# Copy_of_EP1C6T144I8N.net
KiCad netlist of a schematic drawn in Altium Designer
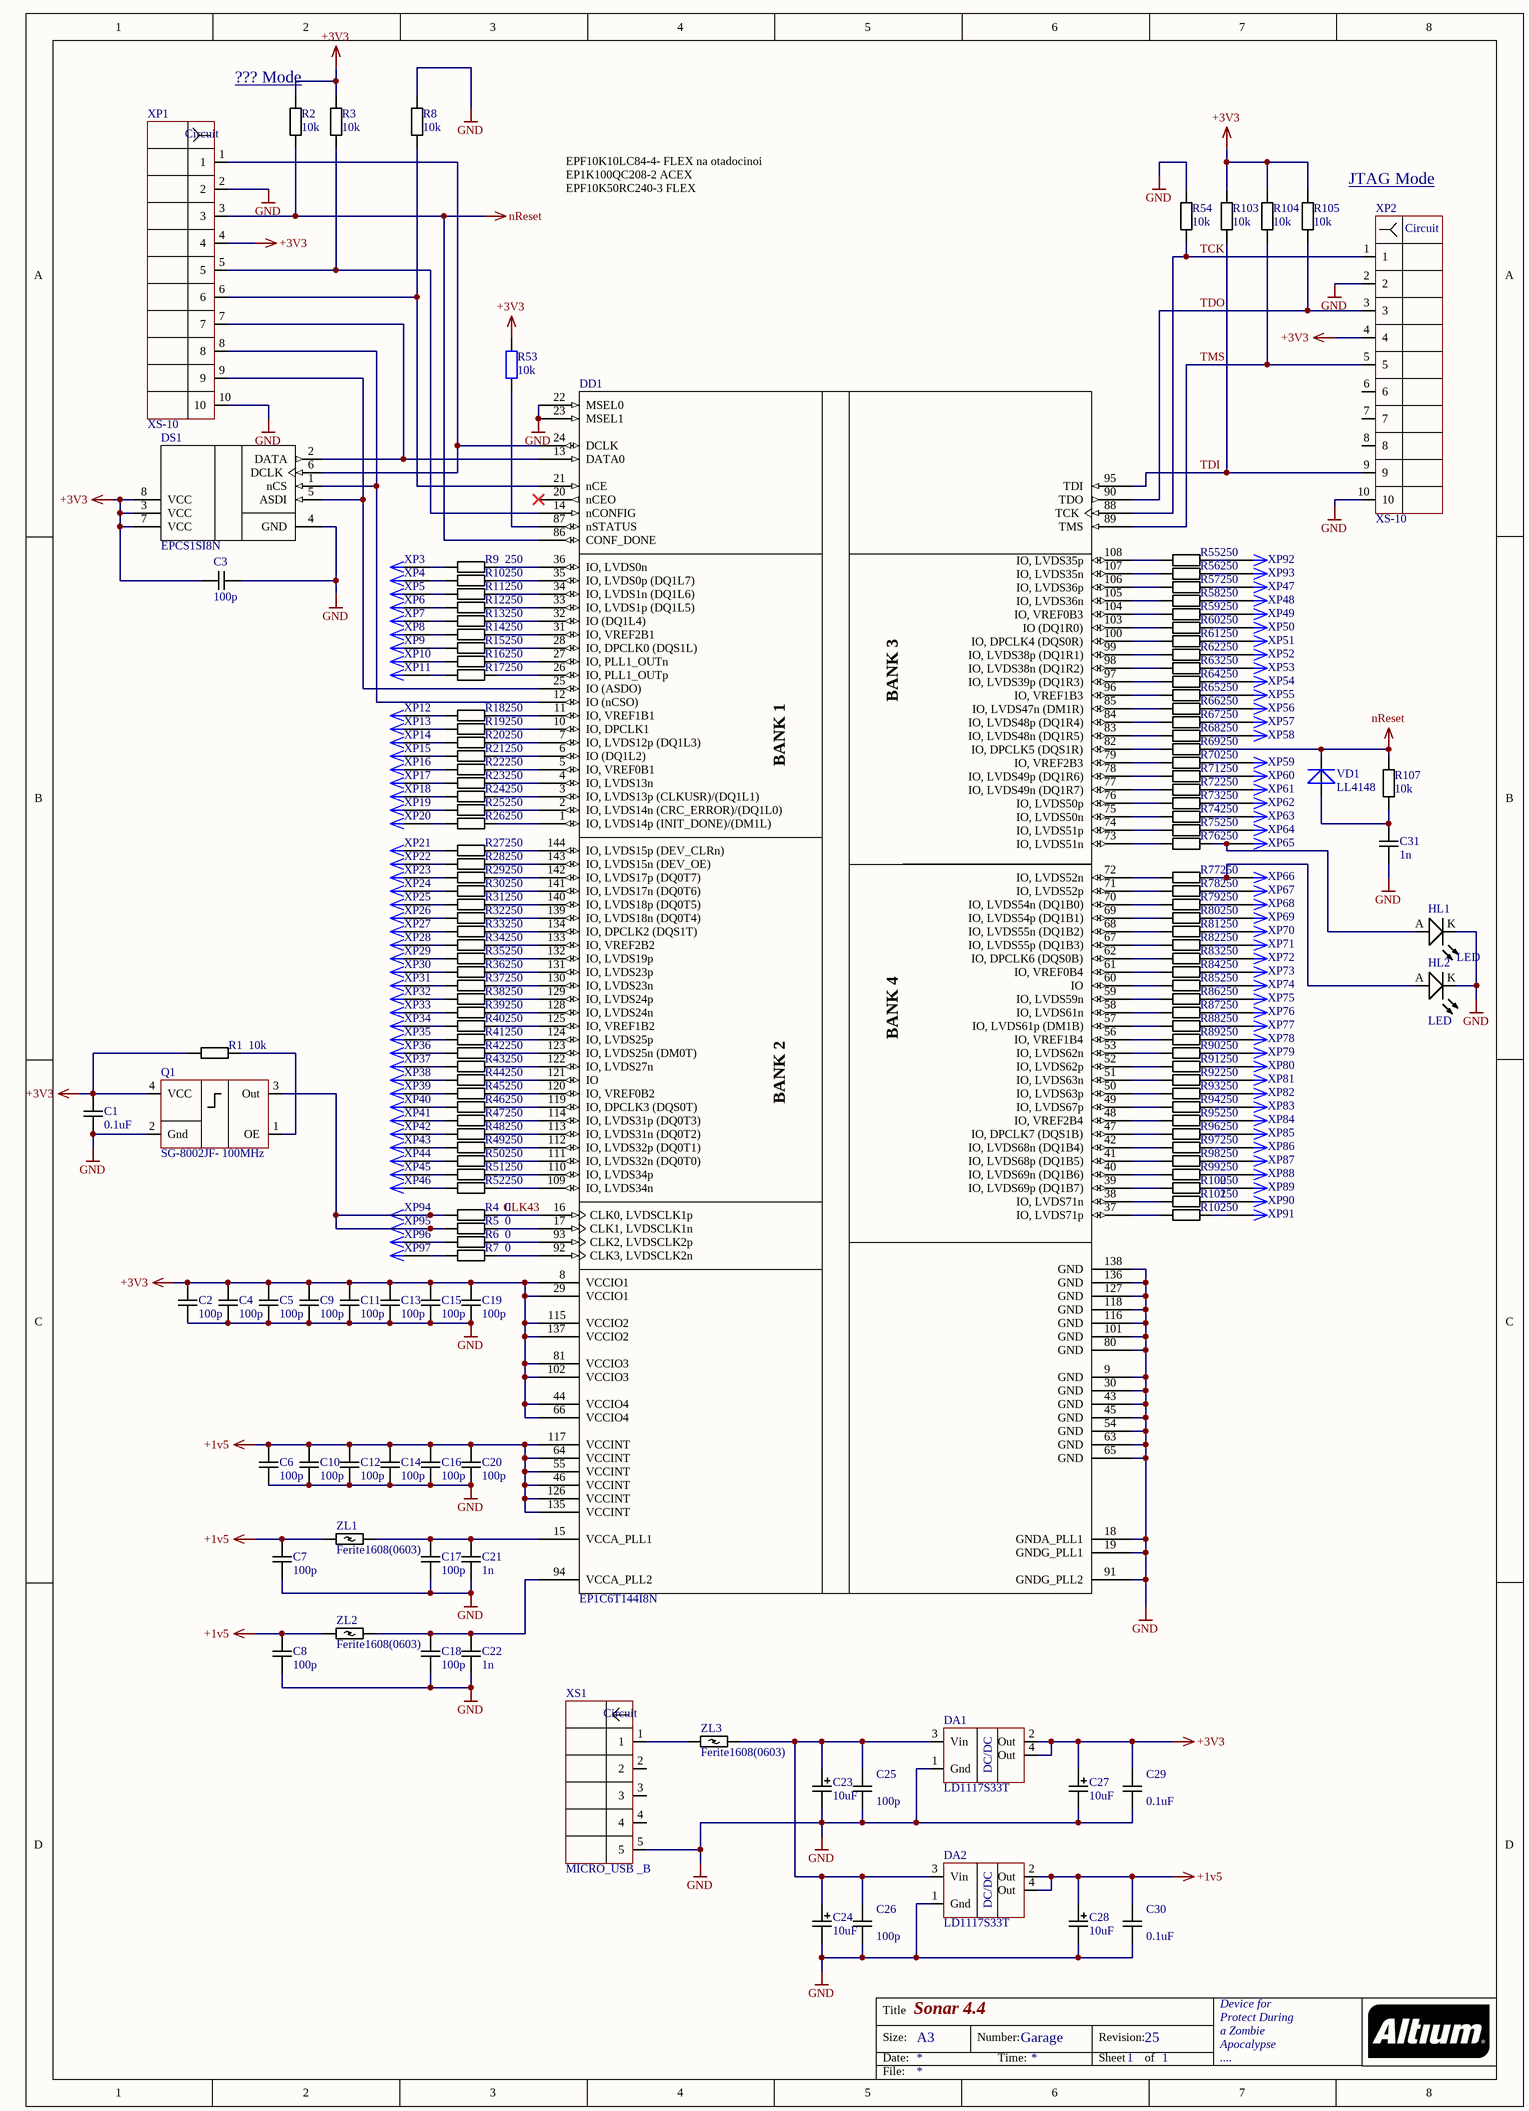
[diagram p0: Copy of EP1C6T144I8N.SchDoc]

(export (version "E")
  (design (tool "Eeschema 10.0.6"))
  (components
    (comp (ref "C1")
      (value "0.1uF")
      (footprint "1005[0402]:CapKemet1005(0402)")
      (fields (field (name "PART NUMBER") "CAPC1005(0402)N") (field (name "DIGI-KEY PART NUMBER") "?"))
      (libsource (lib "ADdatabaseLibfile") (part "Cap"))
    )
    (comp (ref "C2")
      (value "100p")
      (footprint "1005[0402]:CapKemet1005(0402)")
      (fields (field (name "PART NUMBER") "CAPC1005(0402)N") (field (name "DIGI-KEY PART NUMBER") "?"))
      (libsource (lib "ADdatabaseLibfile") (part "Cap"))
    )
    (comp (ref "C3")
      (value "100p")
      (footprint "1005[0402]:CapKemet1005(0402)")
      (fields (field (name "PART NUMBER") "CAPC1005(0402)N") (field (name "DIGI-KEY PART NUMBER") "?"))
      (libsource (lib "ADdatabaseLibfile") (part "Cap"))
    )
    (comp (ref "C4")
      (value "100p")
      (footprint "1005[0402]:CapKemet1005(0402)")
      (fields (field (name "PART NUMBER") "CAPC1005(0402)N") (field (name "DIGI-KEY PART NUMBER") "?"))
      (libsource (lib "ADdatabaseLibfile") (part "Cap"))
    )
    (comp (ref "C5")
      (value "100p")
      (footprint "1005[0402]:CapKemet1005(0402)")
      (fields (field (name "PART NUMBER") "CAPC1005(0402)N") (field (name "DIGI-KEY PART NUMBER") "?"))
      (libsource (lib "ADdatabaseLibfile") (part "Cap"))
    )
    (comp (ref "C6")
      (value "100p")
      (footprint "1005[0402]:CapKemet1005(0402)")
      (fields (field (name "PART NUMBER") "CAPC1005(0402)N") (field (name "DIGI-KEY PART NUMBER") "?"))
      (libsource (lib "ADdatabaseLibfile") (part "Cap"))
    )
    (comp (ref "C7")
      (value "100p")
      (footprint "1005[0402]:CapKemet1005(0402)")
      (fields (field (name "PART NUMBER") "CAPC1005(0402)N") (field (name "DIGI-KEY PART NUMBER") "?"))
      (libsource (lib "ADdatabaseLibfile") (part "Cap"))
    )
    (comp (ref "C8")
      (value "100p")
      (footprint "1005[0402]:CapKemet1005(0402)")
      (fields (field (name "PART NUMBER") "CAPC1005(0402)N") (field (name "DIGI-KEY PART NUMBER") "?"))
      (libsource (lib "ADdatabaseLibfile") (part "Cap"))
    )
    (comp (ref "C9")
      (value "100p")
      (footprint "1005[0402]:CapKemet1005(0402)")
      (fields (field (name "PART NUMBER") "CAPC1005(0402)N") (field (name "DIGI-KEY PART NUMBER") "?"))
      (libsource (lib "ADdatabaseLibfile") (part "Cap"))
    )
    (comp (ref "C10")
      (value "100p")
      (footprint "1005[0402]:CapKemet1005(0402)")
      (fields (field (name "PART NUMBER") "CAPC1005(0402)N") (field (name "DIGI-KEY PART NUMBER") "?"))
      (libsource (lib "ADdatabaseLibfile") (part "Cap"))
    )
    (comp (ref "C11")
      (value "100p")
      (footprint "1005[0402]:CapKemet1005(0402)")
      (fields (field (name "PART NUMBER") "CAPC1005(0402)N") (field (name "DIGI-KEY PART NUMBER") "?"))
      (libsource (lib "ADdatabaseLibfile") (part "Cap"))
    )
    (comp (ref "C12")
      (value "100p")
      (footprint "1005[0402]:CapKemet1005(0402)")
      (fields (field (name "PART NUMBER") "CAPC1005(0402)N") (field (name "DIGI-KEY PART NUMBER") "?"))
      (libsource (lib "ADdatabaseLibfile") (part "Cap"))
    )
    (comp (ref "C13")
      (value "100p")
      (footprint "1005[0402]:CapKemet1005(0402)")
      (fields (field (name "PART NUMBER") "CAPC1005(0402)N") (field (name "DIGI-KEY PART NUMBER") "?"))
      (libsource (lib "ADdatabaseLibfile") (part "Cap"))
    )
    (comp (ref "C14")
      (value "100p")
      (footprint "1005[0402]:CapKemet1005(0402)")
      (fields (field (name "PART NUMBER") "CAPC1005(0402)N") (field (name "DIGI-KEY PART NUMBER") "?"))
      (libsource (lib "ADdatabaseLibfile") (part "Cap"))
    )
    (comp (ref "C15")
      (value "100p")
      (footprint "1005[0402]:CapKemet1005(0402)")
      (fields (field (name "PART NUMBER") "CAPC1005(0402)N") (field (name "DIGI-KEY PART NUMBER") "?"))
      (libsource (lib "ADdatabaseLibfile") (part "Cap"))
    )
    (comp (ref "C16")
      (value "100p")
      (footprint "1005[0402]:CapKemet1005(0402)")
      (fields (field (name "PART NUMBER") "CAPC1005(0402)N") (field (name "DIGI-KEY PART NUMBER") "?"))
      (libsource (lib "ADdatabaseLibfile") (part "Cap"))
    )
    (comp (ref "C17")
      (value "100p")
      (footprint "1005[0402]:CapKemet1005(0402)")
      (fields (field (name "PART NUMBER") "CAPC1005(0402)N") (field (name "DIGI-KEY PART NUMBER") "?"))
      (libsource (lib "ADdatabaseLibfile") (part "Cap"))
    )
    (comp (ref "C18")
      (value "100p")
      (footprint "1005[0402]:CapKemet1005(0402)")
      (fields (field (name "PART NUMBER") "CAPC1005(0402)N") (field (name "DIGI-KEY PART NUMBER") "?"))
      (libsource (lib "ADdatabaseLibfile") (part "Cap"))
    )
    (comp (ref "C19")
      (value "100p")
      (footprint "1005[0402]:CapKemet1005(0402)")
      (fields (field (name "PART NUMBER") "CAPC1005(0402)N") (field (name "DIGI-KEY PART NUMBER") "?"))
      (libsource (lib "ADdatabaseLibfile") (part "Cap"))
    )
    (comp (ref "C20")
      (value "100p")
      (footprint "1005[0402]:CapKemet1005(0402)")
      (fields (field (name "PART NUMBER") "CAPC1005(0402)N") (field (name "DIGI-KEY PART NUMBER") "?"))
      (libsource (lib "ADdatabaseLibfile") (part "Cap"))
    )
    (comp (ref "C21")
      (value "1n")
      (footprint "1005[0402]:CapKemet1005(0402)")
      (fields (field (name "PART NUMBER") "CAPC1005(0402)N") (field (name "DIGI-KEY PART NUMBER") "?"))
      (libsource (lib "ADdatabaseLibfile") (part "Cap"))
    )
    (comp (ref "C22")
      (value "1n")
      (footprint "1005[0402]:CapKemet1005(0402)")
      (fields (field (name "PART NUMBER") "CAPC1005(0402)N") (field (name "DIGI-KEY PART NUMBER") "?"))
      (libsource (lib "ADdatabaseLibfile") (part "Cap"))
    )
    (comp (ref "C23")
      (value "10uF")
      (footprint "0402-A")
      (fields (field (name "PART NUMBER") "CapTantA"))
      (libsource (lib "ADdatabaseLibfile") (part "Cap Pol1"))
    )
    (comp (ref "C24")
      (value "10uF")
      (footprint "0402-A")
      (fields (field (name "PART NUMBER") "CapTantA"))
      (libsource (lib "ADdatabaseLibfile") (part "Cap Pol1"))
    )
    (comp (ref "C25")
      (value "100p")
      (footprint "1005[0402]:CapKemet1005(0402)")
      (fields (field (name "PART NUMBER") "CAPC1005(0402)N") (field (name "DIGI-KEY PART NUMBER") "?"))
      (libsource (lib "ADdatabaseLibfile") (part "Cap"))
    )
    (comp (ref "C26")
      (value "100p")
      (footprint "1005[0402]:CapKemet1005(0402)")
      (fields (field (name "PART NUMBER") "CAPC1005(0402)N") (field (name "DIGI-KEY PART NUMBER") "?"))
      (libsource (lib "ADdatabaseLibfile") (part "Cap"))
    )
    (comp (ref "C27")
      (value "10uF")
      (footprint "0402-A")
      (fields (field (name "PART NUMBER") "CapTantA"))
      (libsource (lib "ADdatabaseLibfile") (part "Cap Pol1"))
    )
    (comp (ref "C28")
      (value "10uF")
      (footprint "0402-A")
      (fields (field (name "PART NUMBER") "CapTantA"))
      (libsource (lib "ADdatabaseLibfile") (part "Cap Pol1"))
    )
    (comp (ref "C29")
      (value "0.1uF")
      (footprint "1005[0402]:CapKemet1005(0402)")
      (fields (field (name "PART NUMBER") "CAPC1005(0402)N") (field (name "DIGI-KEY PART NUMBER") "?"))
      (libsource (lib "ADdatabaseLibfile") (part "Cap"))
    )
    (comp (ref "C30")
      (value "0.1uF")
      (footprint "1005[0402]:CapKemet1005(0402)")
      (fields (field (name "PART NUMBER") "CAPC1005(0402)N") (field (name "DIGI-KEY PART NUMBER") "?"))
      (libsource (lib "ADdatabaseLibfile") (part "Cap"))
    )
    (comp (ref "C31")
      (value "1n")
      (footprint "1005[0402]:CapKemet1005(0402)")
      (fields (field (name "PART NUMBER") "CAPC1005(0402)N") (field (name "DIGI-KEY PART NUMBER") "?"))
      (libsource (lib "ADdatabaseLibfile") (part "Cap"))
    )
    (comp (ref "DA1")
      (value "LD1117S33T")
      (footprint "SOT223_M")
      (libsource (lib "ADdatabaseLibfile") (part "LD1117S33T"))
    )
    (comp (ref "DA2")
      (value "LD1117S33T")
      (footprint "SOT223_M")
      (libsource (lib "ADdatabaseLibfile") (part "LD1117S33T"))
    )
    (comp (ref "DD1")
      (value "EP1C6T144I8N")
      (footprint "TQFP144_N")
      (fields (field (name "PUBLISHER") "Altium Limited"))
      (libsource (lib "SssAccesDatbase") (part "EP1C6T144I8N"))
    )
    (comp (ref "DS1")
      (value "EPCS1SI8N")
      (footprint "SO8_N")
      (description "IC CONFIG DEVICE 1MBIT 8SOIC")
      (fields (field (name "PUBLISHER") "Altium Limited"))
      (libsource (lib "SssAccesDatbase") (part "EPCS1SI8N"))
    )
    (comp (ref "HL1")
      (value "LED")
      (footprint "LED-0603-BLUE")
      (description "LED BLUE DIFFUSED 0603 SMD")
      (fields
        (field (name "PART NUMBER") "LED-0603-BLUE")
        (field (name "DIGI-KEY PART NUMBER") "732-12013-1-ND")
      )
      (libsource (lib "SssAccesDatbase") (part "LED"))
    )
    (comp (ref "HL2")
      (value "LED")
      (footprint "LED-0603-GREEN")
      (description "LED GREEN DIFFUSED 0603 SMD")
      (fields
        (field (name "PART NUMBER") "LED-0603-GREEN")
        (field (name "DIGI-KEY PART NUMBER") "732-12017-1-ND")
      )
      (libsource (lib "SssAccesDatbase") (part "LED"))
    )
    (comp (ref "Q1")
      (value "SG-8002JF- 100MHz")
      (footprint "SG-8002JF")
      (fields (field (name "PART NUMBER") "SG-8002JF"))
      (libsource (lib "ADdatabaseLibfile") (part "SG-8002JF"))
    )
    (comp (ref "R1")
      (value "10k")
      (footprint "1005[0402]:REZKemet 0402")
      (fields (field (name "PART NUMBER") "RESC1005(0402)") (field (name "DIGI-KEY PART NUMBER") "???"))
      (libsource (lib "SssAccesDatbaseDYandex") (part "Resistor general"))
    )
    (comp (ref "R2")
      (value "10k")
      (footprint "1005[0402]:REZKemet 0402")
      (fields (field (name "PART NUMBER") "RESC1005(0402)") (field (name "DIGI-KEY PART NUMBER") "???"))
      (libsource (lib "") (part "Resistor general_1"))
    )
    (comp (ref "R3")
      (value "10k")
      (footprint "1005[0402]:REZKemet 0402")
      (fields (field (name "PART NUMBER") "RESC1005(0402)") (field (name "DIGI-KEY PART NUMBER") "???"))
      (libsource (lib "") (part "Resistor general_1"))
    )
    (comp (ref "R4")
      (value "0")
      (footprint "1005[0402]:REZKemet 0402")
      (fields (field (name "PART NUMBER") "RESC1005(0402)") (field (name "DIGI-KEY PART NUMBER") "???"))
      (libsource (lib "SssAccesDatbaseDYandex") (part "Resistor general"))
    )
    (comp (ref "R5")
      (value "0")
      (footprint "1005[0402]:REZKemet 0402")
      (fields (field (name "PART NUMBER") "RESC1005(0402)") (field (name "DIGI-KEY PART NUMBER") "???"))
      (libsource (lib "SssAccesDatbaseDYandex") (part "Resistor general"))
    )
    (comp (ref "R6")
      (value "0")
      (footprint "1005[0402]:REZKemet 0402")
      (fields (field (name "PART NUMBER") "RESC1005(0402)") (field (name "DIGI-KEY PART NUMBER") "???"))
      (libsource (lib "SssAccesDatbaseDYandex") (part "Resistor general"))
    )
    (comp (ref "R7")
      (value "0")
      (footprint "1005[0402]:REZKemet 0402")
      (fields (field (name "PART NUMBER") "RESC1005(0402)") (field (name "DIGI-KEY PART NUMBER") "???"))
      (libsource (lib "SssAccesDatbaseDYandex") (part "Resistor general"))
    )
    (comp (ref "R8")
      (value "10k")
      (footprint "1005[0402]:REZKemet 0402")
      (fields (field (name "PART NUMBER") "RESC1005(0402)") (field (name "DIGI-KEY PART NUMBER") "???"))
      (libsource (lib "") (part "Resistor general_1"))
    )
    (comp (ref "R9")
      (value "250")
      (footprint "1005[0402]:REZKemet 0402")
      (fields (field (name "PART NUMBER") "RESC1005(0402)") (field (name "DIGI-KEY PART NUMBER") "???"))
      (libsource (lib "SssAccesDatbaseDYandex") (part "Resistor general"))
    )
    (comp (ref "R10")
      (value "250")
      (footprint "1005[0402]:REZKemet 0402")
      (fields (field (name "PART NUMBER") "RESC1005(0402)") (field (name "DIGI-KEY PART NUMBER") "???"))
      (libsource (lib "SssAccesDatbaseDYandex") (part "Resistor general"))
    )
    (comp (ref "R11")
      (value "250")
      (footprint "1005[0402]:REZKemet 0402")
      (fields (field (name "PART NUMBER") "RESC1005(0402)") (field (name "DIGI-KEY PART NUMBER") "???"))
      (libsource (lib "SssAccesDatbaseDYandex") (part "Resistor general"))
    )
    (comp (ref "R12")
      (value "250")
      (footprint "1005[0402]:REZKemet 0402")
      (fields (field (name "PART NUMBER") "RESC1005(0402)") (field (name "DIGI-KEY PART NUMBER") "???"))
      (libsource (lib "SssAccesDatbaseDYandex") (part "Resistor general"))
    )
    (comp (ref "R13")
      (value "250")
      (footprint "1005[0402]:REZKemet 0402")
      (fields (field (name "PART NUMBER") "RESC1005(0402)") (field (name "DIGI-KEY PART NUMBER") "???"))
      (libsource (lib "SssAccesDatbaseDYandex") (part "Resistor general"))
    )
    (comp (ref "R14")
      (value "250")
      (footprint "1005[0402]:REZKemet 0402")
      (fields (field (name "PART NUMBER") "RESC1005(0402)") (field (name "DIGI-KEY PART NUMBER") "???"))
      (libsource (lib "SssAccesDatbaseDYandex") (part "Resistor general"))
    )
    (comp (ref "R15")
      (value "250")
      (footprint "1005[0402]:REZKemet 0402")
      (fields (field (name "PART NUMBER") "RESC1005(0402)") (field (name "DIGI-KEY PART NUMBER") "???"))
      (libsource (lib "SssAccesDatbaseDYandex") (part "Resistor general"))
    )
    (comp (ref "R16")
      (value "250")
      (footprint "1005[0402]:REZKemet 0402")
      (fields (field (name "PART NUMBER") "RESC1005(0402)") (field (name "DIGI-KEY PART NUMBER") "???"))
      (libsource (lib "SssAccesDatbaseDYandex") (part "Resistor general"))
    )
    (comp (ref "R17")
      (value "250")
      (footprint "1005[0402]:REZKemet 0402")
      (fields (field (name "PART NUMBER") "RESC1005(0402)") (field (name "DIGI-KEY PART NUMBER") "???"))
      (libsource (lib "SssAccesDatbaseDYandex") (part "Resistor general"))
    )
    (comp (ref "R18")
      (value "250")
      (footprint "1005[0402]:REZKemet 0402")
      (fields (field (name "PART NUMBER") "RESC1005(0402)") (field (name "DIGI-KEY PART NUMBER") "???"))
      (libsource (lib "SssAccesDatbaseDYandex") (part "Resistor general"))
    )
    (comp (ref "R19")
      (value "250")
      (footprint "1005[0402]:REZKemet 0402")
      (fields (field (name "PART NUMBER") "RESC1005(0402)") (field (name "DIGI-KEY PART NUMBER") "???"))
      (libsource (lib "SssAccesDatbaseDYandex") (part "Resistor general"))
    )
    (comp (ref "R20")
      (value "250")
      (footprint "1005[0402]:REZKemet 0402")
      (fields (field (name "PART NUMBER") "RESC1005(0402)") (field (name "DIGI-KEY PART NUMBER") "???"))
      (libsource (lib "SssAccesDatbaseDYandex") (part "Resistor general"))
    )
    (comp (ref "R21")
      (value "250")
      (footprint "1005[0402]:REZKemet 0402")
      (fields (field (name "PART NUMBER") "RESC1005(0402)") (field (name "DIGI-KEY PART NUMBER") "???"))
      (libsource (lib "SssAccesDatbaseDYandex") (part "Resistor general"))
    )
    (comp (ref "R22")
      (value "250")
      (footprint "1005[0402]:REZKemet 0402")
      (fields (field (name "PART NUMBER") "RESC1005(0402)") (field (name "DIGI-KEY PART NUMBER") "???"))
      (libsource (lib "SssAccesDatbaseDYandex") (part "Resistor general"))
    )
    (comp (ref "R23")
      (value "250")
      (footprint "1005[0402]:REZKemet 0402")
      (fields (field (name "PART NUMBER") "RESC1005(0402)") (field (name "DIGI-KEY PART NUMBER") "???"))
      (libsource (lib "SssAccesDatbaseDYandex") (part "Resistor general"))
    )
    (comp (ref "R24")
      (value "250")
      (footprint "1005[0402]:REZKemet 0402")
      (fields (field (name "PART NUMBER") "RESC1005(0402)") (field (name "DIGI-KEY PART NUMBER") "???"))
      (libsource (lib "SssAccesDatbaseDYandex") (part "Resistor general"))
    )
    (comp (ref "R25")
      (value "250")
      (footprint "1005[0402]:REZKemet 0402")
      (fields (field (name "PART NUMBER") "RESC1005(0402)") (field (name "DIGI-KEY PART NUMBER") "???"))
      (libsource (lib "SssAccesDatbaseDYandex") (part "Resistor general"))
    )
    (comp (ref "R26")
      (value "250")
      (footprint "1005[0402]:REZKemet 0402")
      (fields (field (name "PART NUMBER") "RESC1005(0402)") (field (name "DIGI-KEY PART NUMBER") "???"))
      (libsource (lib "SssAccesDatbaseDYandex") (part "Resistor general"))
    )
    (comp (ref "R27")
      (value "250")
      (footprint "1005[0402]:REZKemet 0402")
      (fields (field (name "PART NUMBER") "RESC1005(0402)") (field (name "DIGI-KEY PART NUMBER") "???"))
      (libsource (lib "SssAccesDatbaseDYandex") (part "Resistor general"))
    )
    (comp (ref "R28")
      (value "250")
      (footprint "1005[0402]:REZKemet 0402")
      (fields (field (name "PART NUMBER") "RESC1005(0402)") (field (name "DIGI-KEY PART NUMBER") "???"))
      (libsource (lib "SssAccesDatbaseDYandex") (part "Resistor general"))
    )
    (comp (ref "R29")
      (value "250")
      (footprint "1005[0402]:REZKemet 0402")
      (fields (field (name "PART NUMBER") "RESC1005(0402)") (field (name "DIGI-KEY PART NUMBER") "???"))
      (libsource (lib "SssAccesDatbaseDYandex") (part "Resistor general"))
    )
    (comp (ref "R30")
      (value "250")
      (footprint "1005[0402]:REZKemet 0402")
      (fields (field (name "PART NUMBER") "RESC1005(0402)") (field (name "DIGI-KEY PART NUMBER") "???"))
      (libsource (lib "SssAccesDatbaseDYandex") (part "Resistor general"))
    )
    (comp (ref "R31")
      (value "250")
      (footprint "1005[0402]:REZKemet 0402")
      (fields (field (name "PART NUMBER") "RESC1005(0402)") (field (name "DIGI-KEY PART NUMBER") "???"))
      (libsource (lib "SssAccesDatbaseDYandex") (part "Resistor general"))
    )
    (comp (ref "R32")
      (value "250")
      (footprint "1005[0402]:REZKemet 0402")
      (fields (field (name "PART NUMBER") "RESC1005(0402)") (field (name "DIGI-KEY PART NUMBER") "???"))
      (libsource (lib "SssAccesDatbaseDYandex") (part "Resistor general"))
    )
    (comp (ref "R33")
      (value "250")
      (footprint "1005[0402]:REZKemet 0402")
      (fields (field (name "PART NUMBER") "RESC1005(0402)") (field (name "DIGI-KEY PART NUMBER") "???"))
      (libsource (lib "SssAccesDatbaseDYandex") (part "Resistor general"))
    )
    (comp (ref "R34")
      (value "250")
      (footprint "1005[0402]:REZKemet 0402")
      (fields (field (name "PART NUMBER") "RESC1005(0402)") (field (name "DIGI-KEY PART NUMBER") "???"))
      (libsource (lib "SssAccesDatbaseDYandex") (part "Resistor general"))
    )
    (comp (ref "R35")
      (value "250")
      (footprint "1005[0402]:REZKemet 0402")
      (fields (field (name "PART NUMBER") "RESC1005(0402)") (field (name "DIGI-KEY PART NUMBER") "???"))
      (libsource (lib "SssAccesDatbaseDYandex") (part "Resistor general"))
    )
    (comp (ref "R36")
      (value "250")
      (footprint "1005[0402]:REZKemet 0402")
      (fields (field (name "PART NUMBER") "RESC1005(0402)") (field (name "DIGI-KEY PART NUMBER") "???"))
      (libsource (lib "SssAccesDatbaseDYandex") (part "Resistor general"))
    )
    (comp (ref "R37")
      (value "250")
      (footprint "1005[0402]:REZKemet 0402")
      (fields (field (name "PART NUMBER") "RESC1005(0402)") (field (name "DIGI-KEY PART NUMBER") "???"))
      (libsource (lib "SssAccesDatbaseDYandex") (part "Resistor general"))
    )
    (comp (ref "R38")
      (value "250")
      (footprint "1005[0402]:REZKemet 0402")
      (fields (field (name "PART NUMBER") "RESC1005(0402)") (field (name "DIGI-KEY PART NUMBER") "???"))
      (libsource (lib "SssAccesDatbaseDYandex") (part "Resistor general"))
    )
    (comp (ref "R39")
      (value "250")
      (footprint "1005[0402]:REZKemet 0402")
      (fields (field (name "PART NUMBER") "RESC1005(0402)") (field (name "DIGI-KEY PART NUMBER") "???"))
      (libsource (lib "SssAccesDatbaseDYandex") (part "Resistor general"))
    )
    (comp (ref "R40")
      (value "250")
      (footprint "1005[0402]:REZKemet 0402")
      (fields (field (name "PART NUMBER") "RESC1005(0402)") (field (name "DIGI-KEY PART NUMBER") "???"))
      (libsource (lib "SssAccesDatbaseDYandex") (part "Resistor general"))
    )
    (comp (ref "R41")
      (value "250")
      (footprint "1005[0402]:REZKemet 0402")
      (fields (field (name "PART NUMBER") "RESC1005(0402)") (field (name "DIGI-KEY PART NUMBER") "???"))
      (libsource (lib "SssAccesDatbaseDYandex") (part "Resistor general"))
    )
    (comp (ref "R42")
      (value "250")
      (footprint "1005[0402]:REZKemet 0402")
      (fields (field (name "PART NUMBER") "RESC1005(0402)") (field (name "DIGI-KEY PART NUMBER") "???"))
      (libsource (lib "SssAccesDatbaseDYandex") (part "Resistor general"))
    )
    (comp (ref "R43")
      (value "250")
      (footprint "1005[0402]:REZKemet 0402")
      (fields (field (name "PART NUMBER") "RESC1005(0402)") (field (name "DIGI-KEY PART NUMBER") "???"))
      (libsource (lib "SssAccesDatbaseDYandex") (part "Resistor general"))
    )
    (comp (ref "R44")
      (value "250")
      (footprint "1005[0402]:REZKemet 0402")
      (fields (field (name "PART NUMBER") "RESC1005(0402)") (field (name "DIGI-KEY PART NUMBER") "???"))
      (libsource (lib "SssAccesDatbaseDYandex") (part "Resistor general"))
    )
    (comp (ref "R45")
      (value "250")
      (footprint "1005[0402]:REZKemet 0402")
      (fields (field (name "PART NUMBER") "RESC1005(0402)") (field (name "DIGI-KEY PART NUMBER") "???"))
      (libsource (lib "SssAccesDatbaseDYandex") (part "Resistor general"))
    )
    (comp (ref "R46")
      (value "250")
      (footprint "1005[0402]:REZKemet 0402")
      (fields (field (name "PART NUMBER") "RESC1005(0402)") (field (name "DIGI-KEY PART NUMBER") "???"))
      (libsource (lib "SssAccesDatbaseDYandex") (part "Resistor general"))
    )
    (comp (ref "R47")
      (value "250")
      (footprint "1005[0402]:REZKemet 0402")
      (fields (field (name "PART NUMBER") "RESC1005(0402)") (field (name "DIGI-KEY PART NUMBER") "???"))
      (libsource (lib "SssAccesDatbaseDYandex") (part "Resistor general"))
    )
    (comp (ref "R48")
      (value "250")
      (footprint "1005[0402]:REZKemet 0402")
      (fields (field (name "PART NUMBER") "RESC1005(0402)") (field (name "DIGI-KEY PART NUMBER") "???"))
      (libsource (lib "SssAccesDatbaseDYandex") (part "Resistor general"))
    )
    (comp (ref "R49")
      (value "250")
      (footprint "1005[0402]:REZKemet 0402")
      (fields (field (name "PART NUMBER") "RESC1005(0402)") (field (name "DIGI-KEY PART NUMBER") "???"))
      (libsource (lib "SssAccesDatbaseDYandex") (part "Resistor general"))
    )
    (comp (ref "R50")
      (value "250")
      (footprint "1005[0402]:REZKemet 0402")
      (fields (field (name "PART NUMBER") "RESC1005(0402)") (field (name "DIGI-KEY PART NUMBER") "???"))
      (libsource (lib "SssAccesDatbaseDYandex") (part "Resistor general"))
    )
    (comp (ref "R51")
      (value "250")
      (footprint "1005[0402]:REZKemet 0402")
      (fields (field (name "PART NUMBER") "RESC1005(0402)") (field (name "DIGI-KEY PART NUMBER") "???"))
      (libsource (lib "SssAccesDatbaseDYandex") (part "Resistor general"))
    )
    (comp (ref "R52")
      (value "250")
      (footprint "1005[0402]:REZKemet 0402")
      (fields (field (name "PART NUMBER") "RESC1005(0402)") (field (name "DIGI-KEY PART NUMBER") "???"))
      (libsource (lib "SssAccesDatbaseDYandex") (part "Resistor general"))
    )
    (comp (ref "R53")
      (value "10k")
      (footprint "1005[0402]:REZKemet 0402")
      (description "Resistor")
      (fields (field (name "PART NUMBER") "RESC1005(0402)") (field (name "DIGI-KEY PART NUMBER") "???"))
      (libsource (lib "ADdatabaseLibfile") (part "Res2"))
    )
    (comp (ref "R54")
      (value "10k")
      (footprint "1005[0402]:REZKemet 0402")
      (fields (field (name "PART NUMBER") "RESC1005(0402)") (field (name "DIGI-KEY PART NUMBER") "???"))
      (libsource (lib "") (part "Resistor general_1"))
    )
    (comp (ref "R55")
      (value "250")
      (footprint "1005[0402]:REZKemet 0402")
      (fields (field (name "PART NUMBER") "RESC1005(0402)") (field (name "DIGI-KEY PART NUMBER") "???"))
      (libsource (lib "SssAccesDatbaseDYandex") (part "Resistor general"))
    )
    (comp (ref "R56")
      (value "250")
      (footprint "1005[0402]:REZKemet 0402")
      (fields (field (name "PART NUMBER") "RESC1005(0402)") (field (name "DIGI-KEY PART NUMBER") "???"))
      (libsource (lib "SssAccesDatbaseDYandex") (part "Resistor general"))
    )
    (comp (ref "R57")
      (value "250")
      (footprint "1005[0402]:REZKemet 0402")
      (fields (field (name "PART NUMBER") "RESC1005(0402)") (field (name "DIGI-KEY PART NUMBER") "???"))
      (libsource (lib "SssAccesDatbaseDYandex") (part "Resistor general"))
    )
    (comp (ref "R58")
      (value "250")
      (footprint "1005[0402]:REZKemet 0402")
      (fields (field (name "PART NUMBER") "RESC1005(0402)") (field (name "DIGI-KEY PART NUMBER") "???"))
      (libsource (lib "SssAccesDatbaseDYandex") (part "Resistor general"))
    )
    (comp (ref "R59")
      (value "250")
      (footprint "1005[0402]:REZKemet 0402")
      (fields (field (name "PART NUMBER") "RESC1005(0402)") (field (name "DIGI-KEY PART NUMBER") "???"))
      (libsource (lib "SssAccesDatbaseDYandex") (part "Resistor general"))
    )
    (comp (ref "R60")
      (value "250")
      (footprint "1005[0402]:REZKemet 0402")
      (fields (field (name "PART NUMBER") "RESC1005(0402)") (field (name "DIGI-KEY PART NUMBER") "???"))
      (libsource (lib "SssAccesDatbaseDYandex") (part "Resistor general"))
    )
    (comp (ref "R61")
      (value "250")
      (footprint "1005[0402]:REZKemet 0402")
      (fields (field (name "PART NUMBER") "RESC1005(0402)") (field (name "DIGI-KEY PART NUMBER") "???"))
      (libsource (lib "SssAccesDatbaseDYandex") (part "Resistor general"))
    )
    (comp (ref "R62")
      (value "250")
      (footprint "1005[0402]:REZKemet 0402")
      (fields (field (name "PART NUMBER") "RESC1005(0402)") (field (name "DIGI-KEY PART NUMBER") "???"))
      (libsource (lib "SssAccesDatbaseDYandex") (part "Resistor general"))
    )
    (comp (ref "R63")
      (value "250")
      (footprint "1005[0402]:REZKemet 0402")
      (fields (field (name "PART NUMBER") "RESC1005(0402)") (field (name "DIGI-KEY PART NUMBER") "???"))
      (libsource (lib "SssAccesDatbaseDYandex") (part "Resistor general"))
    )
    (comp (ref "R64")
      (value "250")
      (footprint "1005[0402]:REZKemet 0402")
      (fields (field (name "PART NUMBER") "RESC1005(0402)") (field (name "DIGI-KEY PART NUMBER") "???"))
      (libsource (lib "SssAccesDatbaseDYandex") (part "Resistor general"))
    )
    (comp (ref "R65")
      (value "250")
      (footprint "1005[0402]:REZKemet 0402")
      (fields (field (name "PART NUMBER") "RESC1005(0402)") (field (name "DIGI-KEY PART NUMBER") "???"))
      (libsource (lib "SssAccesDatbaseDYandex") (part "Resistor general"))
    )
    (comp (ref "R66")
      (value "250")
      (footprint "1005[0402]:REZKemet 0402")
      (fields (field (name "PART NUMBER") "RESC1005(0402)") (field (name "DIGI-KEY PART NUMBER") "???"))
      (libsource (lib "SssAccesDatbaseDYandex") (part "Resistor general"))
    )
    (comp (ref "R67")
      (value "250")
      (footprint "1005[0402]:REZKemet 0402")
      (fields (field (name "PART NUMBER") "RESC1005(0402)") (field (name "DIGI-KEY PART NUMBER") "???"))
      (libsource (lib "SssAccesDatbaseDYandex") (part "Resistor general"))
    )
    (comp (ref "R68")
      (value "250")
      (footprint "1005[0402]:REZKemet 0402")
      (fields (field (name "PART NUMBER") "RESC1005(0402)") (field (name "DIGI-KEY PART NUMBER") "???"))
      (libsource (lib "SssAccesDatbaseDYandex") (part "Resistor general"))
    )
    (comp (ref "R69")
      (value "250")
      (footprint "1005[0402]:REZKemet 0402")
      (fields (field (name "PART NUMBER") "RESC1005(0402)") (field (name "DIGI-KEY PART NUMBER") "???"))
      (libsource (lib "SssAccesDatbaseDYandex") (part "Resistor general"))
    )
    (comp (ref "R70")
      (value "250")
      (footprint "1005[0402]:REZKemet 0402")
      (fields (field (name "PART NUMBER") "RESC1005(0402)") (field (name "DIGI-KEY PART NUMBER") "???"))
      (libsource (lib "SssAccesDatbaseDYandex") (part "Resistor general"))
    )
    (comp (ref "R71")
      (value "250")
      (footprint "1005[0402]:REZKemet 0402")
      (fields (field (name "PART NUMBER") "RESC1005(0402)") (field (name "DIGI-KEY PART NUMBER") "???"))
      (libsource (lib "SssAccesDatbaseDYandex") (part "Resistor general"))
    )
    (comp (ref "R72")
      (value "250")
      (footprint "1005[0402]:REZKemet 0402")
      (fields (field (name "PART NUMBER") "RESC1005(0402)") (field (name "DIGI-KEY PART NUMBER") "???"))
      (libsource (lib "SssAccesDatbaseDYandex") (part "Resistor general"))
    )
    (comp (ref "R73")
      (value "250")
      (footprint "1005[0402]:REZKemet 0402")
      (fields (field (name "PART NUMBER") "RESC1005(0402)") (field (name "DIGI-KEY PART NUMBER") "???"))
      (libsource (lib "SssAccesDatbaseDYandex") (part "Resistor general"))
    )
    (comp (ref "R74")
      (value "250")
      (footprint "1005[0402]:REZKemet 0402")
      (fields (field (name "PART NUMBER") "RESC1005(0402)") (field (name "DIGI-KEY PART NUMBER") "???"))
      (libsource (lib "SssAccesDatbaseDYandex") (part "Resistor general"))
    )
    (comp (ref "R75")
      (value "250")
      (footprint "1005[0402]:REZKemet 0402")
      (fields (field (name "PART NUMBER") "RESC1005(0402)") (field (name "DIGI-KEY PART NUMBER") "???"))
      (libsource (lib "SssAccesDatbaseDYandex") (part "Resistor general"))
    )
    (comp (ref "R76")
      (value "250")
      (footprint "1005[0402]:REZKemet 0402")
      (fields (field (name "PART NUMBER") "RESC1005(0402)") (field (name "DIGI-KEY PART NUMBER") "???"))
      (libsource (lib "SssAccesDatbaseDYandex") (part "Resistor general"))
    )
    (comp (ref "R77")
      (value "250")
      (footprint "1005[0402]:REZKemet 0402")
      (fields (field (name "PART NUMBER") "RESC1005(0402)") (field (name "DIGI-KEY PART NUMBER") "???"))
      (libsource (lib "SssAccesDatbaseDYandex") (part "Resistor general"))
    )
    (comp (ref "R78")
      (value "250")
      (footprint "1005[0402]:REZKemet 0402")
      (fields (field (name "PART NUMBER") "RESC1005(0402)") (field (name "DIGI-KEY PART NUMBER") "???"))
      (libsource (lib "SssAccesDatbaseDYandex") (part "Resistor general"))
    )
    (comp (ref "R79")
      (value "250")
      (footprint "1005[0402]:REZKemet 0402")
      (fields (field (name "PART NUMBER") "RESC1005(0402)") (field (name "DIGI-KEY PART NUMBER") "???"))
      (libsource (lib "SssAccesDatbaseDYandex") (part "Resistor general"))
    )
    (comp (ref "R80")
      (value "250")
      (footprint "1005[0402]:REZKemet 0402")
      (fields (field (name "PART NUMBER") "RESC1005(0402)") (field (name "DIGI-KEY PART NUMBER") "???"))
      (libsource (lib "SssAccesDatbaseDYandex") (part "Resistor general"))
    )
    (comp (ref "R81")
      (value "250")
      (footprint "1005[0402]:REZKemet 0402")
      (fields (field (name "PART NUMBER") "RESC1005(0402)") (field (name "DIGI-KEY PART NUMBER") "???"))
      (libsource (lib "SssAccesDatbaseDYandex") (part "Resistor general"))
    )
    (comp (ref "R82")
      (value "250")
      (footprint "1005[0402]:REZKemet 0402")
      (fields (field (name "PART NUMBER") "RESC1005(0402)") (field (name "DIGI-KEY PART NUMBER") "???"))
      (libsource (lib "SssAccesDatbaseDYandex") (part "Resistor general"))
    )
    (comp (ref "R83")
      (value "250")
      (footprint "1005[0402]:REZKemet 0402")
      (fields (field (name "PART NUMBER") "RESC1005(0402)") (field (name "DIGI-KEY PART NUMBER") "???"))
      (libsource (lib "SssAccesDatbaseDYandex") (part "Resistor general"))
    )
    (comp (ref "R84")
      (value "250")
      (footprint "1005[0402]:REZKemet 0402")
      (fields (field (name "PART NUMBER") "RESC1005(0402)") (field (name "DIGI-KEY PART NUMBER") "???"))
      (libsource (lib "SssAccesDatbaseDYandex") (part "Resistor general"))
    )
    (comp (ref "R85")
      (value "250")
      (footprint "1005[0402]:REZKemet 0402")
      (fields (field (name "PART NUMBER") "RESC1005(0402)") (field (name "DIGI-KEY PART NUMBER") "???"))
      (libsource (lib "SssAccesDatbaseDYandex") (part "Resistor general"))
    )
    (comp (ref "R86")
      (value "250")
      (footprint "1005[0402]:REZKemet 0402")
      (fields (field (name "PART NUMBER") "RESC1005(0402)") (field (name "DIGI-KEY PART NUMBER") "???"))
      (libsource (lib "SssAccesDatbaseDYandex") (part "Resistor general"))
    )
    (comp (ref "R87")
      (value "250")
      (footprint "1005[0402]:REZKemet 0402")
      (fields (field (name "PART NUMBER") "RESC1005(0402)") (field (name "DIGI-KEY PART NUMBER") "???"))
      (libsource (lib "SssAccesDatbaseDYandex") (part "Resistor general"))
    )
    (comp (ref "R88")
      (value "250")
      (footprint "1005[0402]:REZKemet 0402")
      (fields (field (name "PART NUMBER") "RESC1005(0402)") (field (name "DIGI-KEY PART NUMBER") "???"))
      (libsource (lib "SssAccesDatbaseDYandex") (part "Resistor general"))
    )
    (comp (ref "R89")
      (value "250")
      (footprint "1005[0402]:REZKemet 0402")
      (fields (field (name "PART NUMBER") "RESC1005(0402)") (field (name "DIGI-KEY PART NUMBER") "???"))
      (libsource (lib "SssAccesDatbaseDYandex") (part "Resistor general"))
    )
    (comp (ref "R90")
      (value "250")
      (footprint "1005[0402]:REZKemet 0402")
      (fields (field (name "PART NUMBER") "RESC1005(0402)") (field (name "DIGI-KEY PART NUMBER") "???"))
      (libsource (lib "SssAccesDatbaseDYandex") (part "Resistor general"))
    )
    (comp (ref "R91")
      (value "250")
      (footprint "1005[0402]:REZKemet 0402")
      (fields (field (name "PART NUMBER") "RESC1005(0402)") (field (name "DIGI-KEY PART NUMBER") "???"))
      (libsource (lib "SssAccesDatbaseDYandex") (part "Resistor general"))
    )
    (comp (ref "R92")
      (value "250")
      (footprint "1005[0402]:REZKemet 0402")
      (fields (field (name "PART NUMBER") "RESC1005(0402)") (field (name "DIGI-KEY PART NUMBER") "???"))
      (libsource (lib "SssAccesDatbaseDYandex") (part "Resistor general"))
    )
    (comp (ref "R93")
      (value "250")
      (footprint "1005[0402]:REZKemet 0402")
      (fields (field (name "PART NUMBER") "RESC1005(0402)") (field (name "DIGI-KEY PART NUMBER") "???"))
      (libsource (lib "SssAccesDatbaseDYandex") (part "Resistor general"))
    )
    (comp (ref "R94")
      (value "250")
      (footprint "1005[0402]:REZKemet 0402")
      (fields (field (name "PART NUMBER") "RESC1005(0402)") (field (name "DIGI-KEY PART NUMBER") "???"))
      (libsource (lib "SssAccesDatbaseDYandex") (part "Resistor general"))
    )
    (comp (ref "R95")
      (value "250")
      (footprint "1005[0402]:REZKemet 0402")
      (fields (field (name "PART NUMBER") "RESC1005(0402)") (field (name "DIGI-KEY PART NUMBER") "???"))
      (libsource (lib "SssAccesDatbaseDYandex") (part "Resistor general"))
    )
    (comp (ref "R96")
      (value "250")
      (footprint "1005[0402]:REZKemet 0402")
      (fields (field (name "PART NUMBER") "RESC1005(0402)") (field (name "DIGI-KEY PART NUMBER") "???"))
      (libsource (lib "SssAccesDatbaseDYandex") (part "Resistor general"))
    )
    (comp (ref "R97")
      (value "250")
      (footprint "1005[0402]:REZKemet 0402")
      (fields (field (name "PART NUMBER") "RESC1005(0402)") (field (name "DIGI-KEY PART NUMBER") "???"))
      (libsource (lib "SssAccesDatbaseDYandex") (part "Resistor general"))
    )
    (comp (ref "R98")
      (value "250")
      (footprint "1005[0402]:REZKemet 0402")
      (fields (field (name "PART NUMBER") "RESC1005(0402)") (field (name "DIGI-KEY PART NUMBER") "???"))
      (libsource (lib "SssAccesDatbaseDYandex") (part "Resistor general"))
    )
    (comp (ref "R99")
      (value "250")
      (footprint "1005[0402]:REZKemet 0402")
      (fields (field (name "PART NUMBER") "RESC1005(0402)") (field (name "DIGI-KEY PART NUMBER") "???"))
      (libsource (lib "SssAccesDatbaseDYandex") (part "Resistor general"))
    )
    (comp (ref "R100")
      (value "250")
      (footprint "1005[0402]:REZKemet 0402")
      (fields (field (name "PART NUMBER") "RESC1005(0402)") (field (name "DIGI-KEY PART NUMBER") "???"))
      (libsource (lib "SssAccesDatbaseDYandex") (part "Resistor general"))
    )
    (comp (ref "R101")
      (value "250")
      (footprint "1005[0402]:REZKemet 0402")
      (fields (field (name "PART NUMBER") "RESC1005(0402)") (field (name "DIGI-KEY PART NUMBER") "???"))
      (libsource (lib "SssAccesDatbaseDYandex") (part "Resistor general"))
    )
    (comp (ref "R102")
      (value "250")
      (footprint "1005[0402]:REZKemet 0402")
      (fields (field (name "PART NUMBER") "RESC1005(0402)") (field (name "DIGI-KEY PART NUMBER") "???"))
      (libsource (lib "SssAccesDatbaseDYandex") (part "Resistor general"))
    )
    (comp (ref "R103")
      (value "10k")
      (footprint "1005[0402]:REZKemet 0402")
      (fields (field (name "PART NUMBER") "RESC1005(0402)") (field (name "DIGI-KEY PART NUMBER") "???"))
      (libsource (lib "") (part "Resistor general_1"))
    )
    (comp (ref "R104")
      (value "10k")
      (footprint "1005[0402]:REZKemet 0402")
      (fields (field (name "PART NUMBER") "RESC1005(0402)") (field (name "DIGI-KEY PART NUMBER") "???"))
      (libsource (lib "") (part "Resistor general_1"))
    )
    (comp (ref "R105")
      (value "10k")
      (footprint "1005[0402]:REZKemet 0402")
      (fields (field (name "PART NUMBER") "RESC1005(0402)") (field (name "DIGI-KEY PART NUMBER") "???"))
      (libsource (lib "") (part "Resistor general_1"))
    )
    (comp (ref "R107")
      (value "10k")
      (footprint "1005[0402]:REZKemet 0402")
      (fields (field (name "PART NUMBER") "RESC1005(0402)") (field (name "DIGI-KEY PART NUMBER") "???"))
      (libsource (lib "") (part "Resistor general_2"))
    )
    (comp (ref "VD1")
      (value "LL4148")
      (footprint "SOD80")
      (description "Small Signal Diode")
      (fields (field (name "MANUFACTURER PART NUMBER") "?") (field (name "PUBLISHER") "Altium Limited"))
      (libsource (lib "SssAccesDatbaseDYandex") (part "Diode"))
    )
    (comp (ref "XP1")
      (value "XS-10")
      (footprint "ISP 10(1.27mm)")
      (fields
        (field (name "PART NUMBER") "3220-10-0100-00")
        (field (name "DIGI-KEY PART NUMBER") "1175-1627-ND")
      )
      (libsource (lib "") (part "XS-10_1"))
    )
    (comp (ref "XP2")
      (value "XS-10")
      (footprint "ISP 10(1.27mm)")
      (fields
        (field (name "PART NUMBER") "3220-10-0100-00")
        (field (name "DIGI-KEY PART NUMBER") "1175-1627-ND")
      )
      (libsource (lib "ADdatabaseLibfile") (part "XS-10"))
    )
    (comp (ref "XP3")
      (value "P50-B1(DIP)")
      (footprint "Connectors_1,27mm:PLLS1.27-1")
      (libsource (lib "SssAccesDatbase") (part "XP-1_1"))
    )
    (comp (ref "XP4")
      (value "P50-B1(DIP)")
      (footprint "Connectors_1,27mm:PLLS1.27-1")
      (libsource (lib "SssAccesDatbase") (part "XP-1_1"))
    )
    (comp (ref "XP5")
      (value "P50-B1(DIP)")
      (footprint "Connectors_1,27mm:PLLS1.27-1")
      (libsource (lib "SssAccesDatbase") (part "XP-1_1"))
    )
    (comp (ref "XP6")
      (value "P50-B1(DIP)")
      (footprint "Connectors_1,27mm:PLLS1.27-1")
      (libsource (lib "SssAccesDatbase") (part "XP-1_1"))
    )
    (comp (ref "XP7")
      (value "P50-B1(DIP)")
      (footprint "Connectors_1,27mm:PLLS1.27-1")
      (libsource (lib "SssAccesDatbase") (part "XP-1_1"))
    )
    (comp (ref "XP8")
      (value "P50-B1(DIP)")
      (footprint "Connectors_1,27mm:PLLS1.27-1")
      (libsource (lib "SssAccesDatbase") (part "XP-1_1"))
    )
    (comp (ref "XP9")
      (value "P50-B1(DIP)")
      (footprint "Connectors_1,27mm:PLLS1.27-1")
      (libsource (lib "SssAccesDatbase") (part "XP-1_1"))
    )
    (comp (ref "XP10")
      (value "P50-B1(DIP)")
      (footprint "Connectors_1,27mm:PLLS1.27-1")
      (libsource (lib "SssAccesDatbase") (part "XP-1_1"))
    )
    (comp (ref "XP11")
      (value "P50-B1(DIP)")
      (footprint "Connectors_1,27mm:PLLS1.27-1")
      (libsource (lib "SssAccesDatbase") (part "XP-1_1"))
    )
    (comp (ref "XP12")
      (value "P50-B1(DIP)")
      (footprint "Connectors_1,27mm:PLLS1.27-1")
      (libsource (lib "SssAccesDatbase") (part "XP-1_1"))
    )
    (comp (ref "XP13")
      (value "P50-B1(DIP)")
      (footprint "Connectors_1,27mm:PLLS1.27-1")
      (libsource (lib "SssAccesDatbase") (part "XP-1_1"))
    )
    (comp (ref "XP14")
      (value "P50-B1(DIP)")
      (footprint "Connectors_1,27mm:PLLS1.27-1")
      (libsource (lib "SssAccesDatbase") (part "XP-1_1"))
    )
    (comp (ref "XP15")
      (value "P50-B1(DIP)")
      (footprint "Connectors_1,27mm:PLLS1.27-1")
      (libsource (lib "SssAccesDatbase") (part "XP-1_1"))
    )
    (comp (ref "XP16")
      (value "P50-B1(DIP)")
      (footprint "Connectors_1,27mm:PLLS1.27-1")
      (libsource (lib "SssAccesDatbase") (part "XP-1_1"))
    )
    (comp (ref "XP17")
      (value "P50-B1(DIP)")
      (footprint "Connectors_1,27mm:PLLS1.27-1")
      (libsource (lib "SssAccesDatbase") (part "XP-1_1"))
    )
    (comp (ref "XP18")
      (value "P50-B1(DIP)")
      (footprint "Connectors_1,27mm:PLLS1.27-1")
      (libsource (lib "SssAccesDatbase") (part "XP-1_1"))
    )
    (comp (ref "XP19")
      (value "P50-B1(DIP)")
      (footprint "Connectors_1,27mm:PLLS1.27-1")
      (libsource (lib "SssAccesDatbase") (part "XP-1_1"))
    )
    (comp (ref "XP20")
      (value "P50-B1(DIP)")
      (footprint "Connectors_1,27mm:PLLS1.27-1")
      (libsource (lib "SssAccesDatbase") (part "XP-1_1"))
    )
    (comp (ref "XP21")
      (value "P50-B1(DIP)")
      (footprint "Connectors_1,27mm:PLLS1.27-1")
      (libsource (lib "SssAccesDatbase") (part "XP-1_1"))
    )
    (comp (ref "XP22")
      (value "P50-B1(DIP)")
      (footprint "Connectors_1,27mm:PLLS1.27-1")
      (libsource (lib "SssAccesDatbase") (part "XP-1_1"))
    )
    (comp (ref "XP23")
      (value "P50-B1(DIP)")
      (footprint "Connectors_1,27mm:PLLS1.27-1")
      (libsource (lib "SssAccesDatbase") (part "XP-1_1"))
    )
    (comp (ref "XP24")
      (value "P50-B1(DIP)")
      (footprint "Connectors_1,27mm:PLLS1.27-1")
      (libsource (lib "SssAccesDatbase") (part "XP-1_1"))
    )
    (comp (ref "XP25")
      (value "P50-B1(DIP)")
      (footprint "Connectors_1,27mm:PLLS1.27-1")
      (libsource (lib "SssAccesDatbase") (part "XP-1_1"))
    )
    (comp (ref "XP26")
      (value "P50-B1(DIP)")
      (footprint "Connectors_1,27mm:PLLS1.27-1")
      (libsource (lib "SssAccesDatbase") (part "XP-1_1"))
    )
    (comp (ref "XP27")
      (value "P50-B1(DIP)")
      (footprint "Connectors_1,27mm:PLLS1.27-1")
      (libsource (lib "SssAccesDatbase") (part "XP-1_1"))
    )
    (comp (ref "XP28")
      (value "P50-B1(DIP)")
      (footprint "Connectors_1,27mm:PLLS1.27-1")
      (libsource (lib "SssAccesDatbase") (part "XP-1_1"))
    )
    (comp (ref "XP29")
      (value "P50-B1(DIP)")
      (footprint "Connectors_1,27mm:PLLS1.27-1")
      (libsource (lib "SssAccesDatbase") (part "XP-1_1"))
    )
    (comp (ref "XP30")
      (value "P50-B1(DIP)")
      (footprint "Connectors_1,27mm:PLLS1.27-1")
      (libsource (lib "SssAccesDatbase") (part "XP-1_1"))
    )
    (comp (ref "XP31")
      (value "P50-B1(DIP)")
      (footprint "Connectors_1,27mm:PLLS1.27-1")
      (libsource (lib "SssAccesDatbase") (part "XP-1_1"))
    )
    (comp (ref "XP32")
      (value "P50-B1(DIP)")
      (footprint "Connectors_1,27mm:PLLS1.27-1")
      (libsource (lib "SssAccesDatbase") (part "XP-1_1"))
    )
    (comp (ref "XP33")
      (value "P50-B1(DIP)")
      (footprint "Connectors_1,27mm:PLLS1.27-1")
      (libsource (lib "SssAccesDatbase") (part "XP-1_1"))
    )
    (comp (ref "XP34")
      (value "P50-B1(DIP)")
      (footprint "Connectors_1,27mm:PLLS1.27-1")
      (libsource (lib "SssAccesDatbase") (part "XP-1_1"))
    )
    (comp (ref "XP35")
      (value "P50-B1(DIP)")
      (footprint "Connectors_1,27mm:PLLS1.27-1")
      (libsource (lib "SssAccesDatbase") (part "XP-1_1"))
    )
    (comp (ref "XP36")
      (value "P50-B1(DIP)")
      (footprint "Connectors_1,27mm:PLLS1.27-1")
      (libsource (lib "SssAccesDatbase") (part "XP-1_1"))
    )
    (comp (ref "XP37")
      (value "P50-B1(DIP)")
      (footprint "Connectors_1,27mm:PLLS1.27-1")
      (libsource (lib "SssAccesDatbase") (part "XP-1_1"))
    )
    (comp (ref "XP38")
      (value "P50-B1(DIP)")
      (footprint "Connectors_1,27mm:PLLS1.27-1")
      (libsource (lib "SssAccesDatbase") (part "XP-1_1"))
    )
    (comp (ref "XP39")
      (value "P50-B1(DIP)")
      (footprint "Connectors_1,27mm:PLLS1.27-1")
      (libsource (lib "SssAccesDatbase") (part "XP-1_1"))
    )
    (comp (ref "XP40")
      (value "P50-B1(DIP)")
      (footprint "Connectors_1,27mm:PLLS1.27-1")
      (libsource (lib "SssAccesDatbase") (part "XP-1_1"))
    )
    (comp (ref "XP41")
      (value "P50-B1(DIP)")
      (footprint "Connectors_1,27mm:PLLS1.27-1")
      (libsource (lib "SssAccesDatbase") (part "XP-1_1"))
    )
    (comp (ref "XP42")
      (value "P50-B1(DIP)")
      (footprint "Connectors_1,27mm:PLLS1.27-1")
      (libsource (lib "SssAccesDatbase") (part "XP-1_1"))
    )
    (comp (ref "XP43")
      (value "P50-B1(DIP)")
      (footprint "Connectors_1,27mm:PLLS1.27-1")
      (libsource (lib "SssAccesDatbase") (part "XP-1_1"))
    )
    (comp (ref "XP44")
      (value "P50-B1(DIP)")
      (footprint "Connectors_1,27mm:PLLS1.27-1")
      (libsource (lib "SssAccesDatbase") (part "XP-1_1"))
    )
    (comp (ref "XP45")
      (value "P50-B1(DIP)")
      (footprint "Connectors_1,27mm:PLLS1.27-1")
      (libsource (lib "SssAccesDatbase") (part "XP-1_1"))
    )
    (comp (ref "XP46")
      (value "P50-B1(DIP)")
      (footprint "Connectors_1,27mm:PLLS1.27-1")
      (libsource (lib "SssAccesDatbase") (part "XP-1_1"))
    )
    (comp (ref "XP47")
      (value "P50-B1(DIP)")
      (footprint "Connectors_1,27mm:PLLS1.27-1")
      (libsource (lib "SssAccesDatbase") (part "XP-1_1"))
    )
    (comp (ref "XP48")
      (value "P50-B1(DIP)")
      (footprint "Connectors_1,27mm:PLLS1.27-1")
      (libsource (lib "SssAccesDatbase") (part "XP-1_1"))
    )
    (comp (ref "XP49")
      (value "P50-B1(DIP)")
      (footprint "Connectors_1,27mm:PLLS1.27-1")
      (libsource (lib "SssAccesDatbase") (part "XP-1_1"))
    )
    (comp (ref "XP50")
      (value "P50-B1(DIP)")
      (footprint "Connectors_1,27mm:PLLS1.27-1")
      (libsource (lib "SssAccesDatbase") (part "XP-1_1"))
    )
    (comp (ref "XP51")
      (value "P50-B1(DIP)")
      (footprint "Connectors_1,27mm:PLLS1.27-1")
      (libsource (lib "SssAccesDatbase") (part "XP-1_1"))
    )
    (comp (ref "XP52")
      (value "P50-B1(DIP)")
      (footprint "Connectors_1,27mm:PLLS1.27-1")
      (libsource (lib "SssAccesDatbase") (part "XP-1_1"))
    )
    (comp (ref "XP53")
      (value "P50-B1(DIP)")
      (footprint "Connectors_1,27mm:PLLS1.27-1")
      (libsource (lib "SssAccesDatbase") (part "XP-1_1"))
    )
    (comp (ref "XP54")
      (value "P50-B1(DIP)")
      (footprint "Connectors_1,27mm:PLLS1.27-1")
      (libsource (lib "SssAccesDatbase") (part "XP-1_1"))
    )
    (comp (ref "XP55")
      (value "P50-B1(DIP)")
      (footprint "Connectors_1,27mm:PLLS1.27-1")
      (libsource (lib "SssAccesDatbase") (part "XP-1_1"))
    )
    (comp (ref "XP56")
      (value "P50-B1(DIP)")
      (footprint "Connectors_1,27mm:PLLS1.27-1")
      (libsource (lib "SssAccesDatbase") (part "XP-1_1"))
    )
    (comp (ref "XP57")
      (value "P50-B1(DIP)")
      (footprint "Connectors_1,27mm:PLLS1.27-1")
      (libsource (lib "SssAccesDatbase") (part "XP-1_1"))
    )
    (comp (ref "XP58")
      (value "P50-B1(DIP)")
      (footprint "Connectors_1,27mm:PLLS1.27-1")
      (libsource (lib "SssAccesDatbase") (part "XP-1_1"))
    )
    (comp (ref "XP59")
      (value "P50-B1(DIP)")
      (footprint "Connectors_1,27mm:PLLS1.27-1")
      (libsource (lib "SssAccesDatbase") (part "XP-1_1"))
    )
    (comp (ref "XP60")
      (value "P50-B1(DIP)")
      (footprint "Connectors_1,27mm:PLLS1.27-1")
      (libsource (lib "SssAccesDatbase") (part "XP-1_1"))
    )
    (comp (ref "XP61")
      (value "P50-B1(DIP)")
      (footprint "Connectors_1,27mm:PLLS1.27-1")
      (libsource (lib "SssAccesDatbase") (part "XP-1_1"))
    )
    (comp (ref "XP62")
      (value "P50-B1(DIP)")
      (footprint "Connectors_1,27mm:PLLS1.27-1")
      (libsource (lib "SssAccesDatbase") (part "XP-1_1"))
    )
    (comp (ref "XP63")
      (value "P50-B1(DIP)")
      (footprint "Connectors_1,27mm:PLLS1.27-1")
      (libsource (lib "SssAccesDatbase") (part "XP-1_1"))
    )
    (comp (ref "XP64")
      (value "P50-B1(DIP)")
      (footprint "Connectors_1,27mm:PLLS1.27-1")
      (libsource (lib "SssAccesDatbase") (part "XP-1_1"))
    )
    (comp (ref "XP65")
      (value "P50-B1(DIP)")
      (footprint "Connectors_1,27mm:PLLS1.27-1")
      (libsource (lib "SssAccesDatbase") (part "XP-1_1"))
    )
    (comp (ref "XP66")
      (value "P50-B1(DIP)")
      (footprint "Connectors_1,27mm:PLLS1.27-1")
      (libsource (lib "SssAccesDatbase") (part "XP-1_1"))
    )
    (comp (ref "XP67")
      (value "P50-B1(DIP)")
      (footprint "Connectors_1,27mm:PLLS1.27-1")
      (libsource (lib "SssAccesDatbase") (part "XP-1_1"))
    )
    (comp (ref "XP68")
      (value "P50-B1(DIP)")
      (footprint "Connectors_1,27mm:PLLS1.27-1")
      (libsource (lib "SssAccesDatbase") (part "XP-1_1"))
    )
    (comp (ref "XP69")
      (value "P50-B1(DIP)")
      (footprint "Connectors_1,27mm:PLLS1.27-1")
      (libsource (lib "SssAccesDatbase") (part "XP-1_1"))
    )
    (comp (ref "XP70")
      (value "P50-B1(DIP)")
      (footprint "Connectors_1,27mm:PLLS1.27-1")
      (libsource (lib "SssAccesDatbase") (part "XP-1_1"))
    )
    (comp (ref "XP71")
      (value "P50-B1(DIP)")
      (footprint "Connectors_1,27mm:PLLS1.27-1")
      (libsource (lib "SssAccesDatbase") (part "XP-1_1"))
    )
    (comp (ref "XP72")
      (value "P50-B1(DIP)")
      (footprint "Connectors_1,27mm:PLLS1.27-1")
      (libsource (lib "SssAccesDatbase") (part "XP-1_1"))
    )
    (comp (ref "XP73")
      (value "P50-B1(DIP)")
      (footprint "Connectors_1,27mm:PLLS1.27-1")
      (libsource (lib "SssAccesDatbase") (part "XP-1_1"))
    )
    (comp (ref "XP74")
      (value "P50-B1(DIP)")
      (footprint "Connectors_1,27mm:PLLS1.27-1")
      (libsource (lib "SssAccesDatbase") (part "XP-1_1"))
    )
    (comp (ref "XP75")
      (value "P50-B1(DIP)")
      (footprint "Connectors_1,27mm:PLLS1.27-1")
      (libsource (lib "SssAccesDatbase") (part "XP-1_1"))
    )
    (comp (ref "XP76")
      (value "P50-B1(DIP)")
      (footprint "Connectors_1,27mm:PLLS1.27-1")
      (libsource (lib "SssAccesDatbase") (part "XP-1_1"))
    )
    (comp (ref "XP77")
      (value "P50-B1(DIP)")
      (footprint "Connectors_1,27mm:PLLS1.27-1")
      (libsource (lib "SssAccesDatbase") (part "XP-1_1"))
    )
    (comp (ref "XP78")
      (value "P50-B1(DIP)")
      (footprint "Connectors_1,27mm:PLLS1.27-1")
      (libsource (lib "SssAccesDatbase") (part "XP-1_1"))
    )
    (comp (ref "XP79")
      (value "P50-B1(DIP)")
      (footprint "Connectors_1,27mm:PLLS1.27-1")
      (libsource (lib "SssAccesDatbase") (part "XP-1_1"))
    )
    (comp (ref "XP80")
      (value "P50-B1(DIP)")
      (footprint "Connectors_1,27mm:PLLS1.27-1")
      (libsource (lib "SssAccesDatbase") (part "XP-1_1"))
    )
    (comp (ref "XP81")
      (value "P50-B1(DIP)")
      (footprint "Connectors_1,27mm:PLLS1.27-1")
      (libsource (lib "SssAccesDatbase") (part "XP-1_1"))
    )
    (comp (ref "XP82")
      (value "P50-B1(DIP)")
      (footprint "Connectors_1,27mm:PLLS1.27-1")
      (libsource (lib "SssAccesDatbase") (part "XP-1_1"))
    )
    (comp (ref "XP83")
      (value "P50-B1(DIP)")
      (footprint "Connectors_1,27mm:PLLS1.27-1")
      (libsource (lib "SssAccesDatbase") (part "XP-1_1"))
    )
    (comp (ref "XP84")
      (value "P50-B1(DIP)")
      (footprint "Connectors_1,27mm:PLLS1.27-1")
      (libsource (lib "SssAccesDatbase") (part "XP-1_1"))
    )
    (comp (ref "XP85")
      (value "P50-B1(DIP)")
      (footprint "Connectors_1,27mm:PLLS1.27-1")
      (libsource (lib "SssAccesDatbase") (part "XP-1_1"))
    )
    (comp (ref "XP86")
      (value "P50-B1(DIP)")
      (footprint "Connectors_1,27mm:PLLS1.27-1")
      (libsource (lib "SssAccesDatbase") (part "XP-1_1"))
    )
    (comp (ref "XP87")
      (value "P50-B1(DIP)")
      (footprint "Connectors_1,27mm:PLLS1.27-1")
      (libsource (lib "SssAccesDatbase") (part "XP-1_1"))
    )
    (comp (ref "XP88")
      (value "P50-B1(DIP)")
      (footprint "Connectors_1,27mm:PLLS1.27-1")
      (libsource (lib "SssAccesDatbase") (part "XP-1_1"))
    )
    (comp (ref "XP89")
      (value "P50-B1(DIP)")
      (footprint "Connectors_1,27mm:PLLS1.27-1")
      (libsource (lib "SssAccesDatbase") (part "XP-1_1"))
    )
    (comp (ref "XP90")
      (value "P50-B1(DIP)")
      (footprint "Connectors_1,27mm:PLLS1.27-1")
      (libsource (lib "SssAccesDatbase") (part "XP-1_1"))
    )
    (comp (ref "XP91")
      (value "P50-B1(DIP)")
      (footprint "Connectors_1,27mm:PLLS1.27-1")
      (libsource (lib "SssAccesDatbase") (part "XP-1_1"))
    )
    (comp (ref "XP92")
      (value "PLLS1.27-1")
      (footprint "PLLS1.27-1")
      (libsource (lib "SssAccesDatbase") (part "XP-1_1"))
    )
    (comp (ref "XP93")
      (value "PLLS1.27-1")
      (footprint "PLLS1.27-1")
      (libsource (lib "SssAccesDatbase") (part "XP-1_1"))
    )
    (comp (ref "XP94")
      (value "PLLS1.27-1")
      (footprint "PLLS1.27-1")
      (libsource (lib "SssAccesDatbase") (part "XP-1_1"))
    )
    (comp (ref "XP95")
      (value "PLLS1.27-1")
      (footprint "PLLS1.27-1")
      (libsource (lib "SssAccesDatbase") (part "XP-1_1"))
    )
    (comp (ref "XP96")
      (value "PLLS1.27-1")
      (footprint "PLLS1.27-1")
      (libsource (lib "SssAccesDatbase") (part "XP-1_1"))
    )
    (comp (ref "XP97")
      (value "PLLS1.27-1")
      (footprint "PLLS1.27-1")
      (libsource (lib "SssAccesDatbase") (part "XP-1_1"))
    )
    (comp (ref "XS1")
      (value "MICRO_USB _B")
      (footprint "MICRO_USB _B")
      (fields (field (name "DIGI-KEY PART NUMBER") "???"))
      (libsource (lib "SssAccesDatbase") (part "Micro USB"))
    )
    (comp (ref "ZL1")
      (value "Ferite1608(0603)")
      (footprint "INDC1608(0603)N")
      (description "ferite bead")
      (fields (field (name "DIGI-KEY PART NUMBER") "???"))
      (libsource (lib "SssAccesDatbase") (part "ZL"))
    )
    (comp (ref "ZL2")
      (value "Ferite1608(0603)")
      (footprint "INDC1608(0603)N")
      (description "ferite bead")
      (fields (field (name "DIGI-KEY PART NUMBER") "???"))
      (libsource (lib "SssAccesDatbase") (part "ZL"))
    )
    (comp (ref "ZL3")
      (value "Ferite1608(0603)")
      (footprint "INDC1608(0603)N")
      (description "ferite bead")
      (fields (field (name "DIGI-KEY PART NUMBER") "???"))
      (libsource (lib "SssAccesDatbase") (part "ZL"))
    )
  )
  (nets
    (net (code "1") (name "+1v5") (class "Default")
      (node (ref "C10") (pin "1") (pinfunction "1_1") (pintype "passive"))
      (node (ref "C12") (pin "1") (pinfunction "1_1") (pintype "passive"))
      (node (ref "C14") (pin "1") (pinfunction "1_1") (pintype "passive"))
      (node (ref "C16") (pin "1") (pinfunction "1_1") (pintype "passive"))
      (node (ref "C20") (pin "1") (pinfunction "1_1") (pintype "passive"))
      (node (ref "C28") (pin "1") (pinfunction "1_1") (pintype "passive"))
      (node (ref "C30") (pin "2") (pinfunction "2_2") (pintype "passive"))
      (node (ref "C6") (pin "1") (pinfunction "1_1") (pintype "passive"))
      (node (ref "C7") (pin "1") (pinfunction "1_1") (pintype "passive"))
      (node (ref "C8") (pin "1") (pinfunction "1_1") (pintype "passive"))
      (node (ref "DA2") (pin "2") (pinfunction "Out_2") (pintype "passive"))
      (node (ref "DA2") (pin "4") (pinfunction "Out_4") (pintype "passive"))
      (node (ref "DD1") (pin "117") (pinfunction "VCCINT_117") (pintype "power_in"))
      (node (ref "DD1") (pin "126") (pinfunction "VCCINT_126") (pintype "power_in"))
      (node (ref "DD1") (pin "135") (pinfunction "VCCINT_135") (pintype "power_in"))
      (node (ref "DD1") (pin "46") (pinfunction "VCCINT_46") (pintype "power_in"))
      (node (ref "DD1") (pin "55") (pinfunction "VCCINT_55") (pintype "power_in"))
      (node (ref "DD1") (pin "64") (pinfunction "VCCINT_64") (pintype "power_in"))
      (node (ref "ZL1") (pin "1") (pinfunction "1_1") (pintype "passive"))
      (node (ref "ZL2") (pin "1") (pinfunction "1_1") (pintype "passive"))
    )
    (net (code "2") (name "+3V3") (class "Default")
      (node (ref "C1") (pin "2") (pinfunction "2_2") (pintype "passive"))
      (node (ref "C11") (pin "1") (pinfunction "1_1") (pintype "passive"))
      (node (ref "C13") (pin "1") (pinfunction "1_1") (pintype "passive"))
      (node (ref "C15") (pin "1") (pinfunction "1_1") (pintype "passive"))
      (node (ref "C19") (pin "1") (pinfunction "1_1") (pintype "passive"))
      (node (ref "C2") (pin "1") (pinfunction "1_1") (pintype "passive"))
      (node (ref "C27") (pin "1") (pinfunction "1_1") (pintype "passive"))
      (node (ref "C29") (pin "2") (pinfunction "2_2") (pintype "passive"))
      (node (ref "C3") (pin "2") (pinfunction "2_2") (pintype "passive"))
      (node (ref "C4") (pin "1") (pinfunction "1_1") (pintype "passive"))
      (node (ref "C5") (pin "1") (pinfunction "1_1") (pintype "passive"))
      (node (ref "C9") (pin "1") (pinfunction "1_1") (pintype "passive"))
      (node (ref "DA1") (pin "2") (pinfunction "Out_2") (pintype "passive"))
      (node (ref "DA1") (pin "4") (pinfunction "Out_4") (pintype "passive"))
      (node (ref "DD1") (pin "102") (pinfunction "VCCIO3_102") (pintype "power_in"))
      (node (ref "DD1") (pin "115") (pinfunction "VCCIO2_115") (pintype "power_in"))
      (node (ref "DD1") (pin "137") (pinfunction "VCCIO2_137") (pintype "power_in"))
      (node (ref "DD1") (pin "29") (pinfunction "VCCIO1_29") (pintype "power_in"))
      (node (ref "DD1") (pin "44") (pinfunction "VCCIO4_44") (pintype "power_in"))
      (node (ref "DD1") (pin "66") (pinfunction "VCCIO4_66") (pintype "power_in"))
      (node (ref "DD1") (pin "8") (pinfunction "VCCIO1_8") (pintype "power_in"))
      (node (ref "DD1") (pin "81") (pinfunction "VCCIO3_81") (pintype "power_in"))
      (node (ref "DS1") (pin "3") (pinfunction "VCC_3") (pintype "power_in"))
      (node (ref "DS1") (pin "7") (pinfunction "VCC_7") (pintype "power_in"))
      (node (ref "DS1") (pin "8") (pinfunction "VCC_8") (pintype "power_in"))
      (node (ref "Q1") (pin "4") (pinfunction "VCC_4") (pintype "passive"))
      (node (ref "R1") (pin "1") (pinfunction "1_1") (pintype "passive"))
      (node (ref "R103") (pin "2") (pinfunction "2_2") (pintype "passive"))
      (node (ref "R104") (pin "2") (pinfunction "2_2") (pintype "passive"))
      (node (ref "R105") (pin "2") (pinfunction "2_2") (pintype "passive"))
      (node (ref "R2") (pin "2") (pinfunction "2_2") (pintype "passive"))
      (node (ref "R3") (pin "2") (pinfunction "2_2") (pintype "passive"))
      (node (ref "R53") (pin "2") (pinfunction "2_2") (pintype "passive"))
      (node (ref "XP1") (pin "4") (pinfunction "4_4") (pintype "passive"))
      (node (ref "XP2") (pin "4") (pinfunction "4_4") (pintype "passive"))
    )
    (net (code "3") (name "/CLK43") (class "Default")
      (node (ref "DD1") (pin "16") (pinfunction "CLK0,_LVDSCLK1p_16") (pintype "input"))
      (node (ref "R4") (pin "2") (pinfunction "2_2") (pintype "passive"))
    )
    (net (code "4") (name "/TCK") (class "Default")
      (node (ref "DD1") (pin "88") (pinfunction "TCK_88") (pintype "input"))
      (node (ref "R54") (pin "1") (pinfunction "1_1") (pintype "passive"))
      (node (ref "XP2") (pin "1") (pinfunction "1_1") (pintype "passive"))
    )
    (net (code "5") (name "/TDI") (class "Default")
      (node (ref "DD1") (pin "95") (pinfunction "TDI_95") (pintype "input"))
      (node (ref "R103") (pin "1") (pinfunction "1_1") (pintype "passive"))
      (node (ref "XP2") (pin "9") (pinfunction "9_9") (pintype "passive"))
    )
    (net (code "6") (name "/TDO") (class "Default")
      (node (ref "DD1") (pin "90") (pinfunction "TDO_90") (pintype "output"))
      (node (ref "R105") (pin "1") (pinfunction "1_1") (pintype "passive"))
      (node (ref "XP2") (pin "3") (pinfunction "3_3") (pintype "passive"))
    )
    (net (code "7") (name "/TMS") (class "Default")
      (node (ref "DD1") (pin "89") (pinfunction "TMS_89") (pintype "input"))
      (node (ref "R104") (pin "1") (pinfunction "1_1") (pintype "passive"))
      (node (ref "XP2") (pin "5") (pinfunction "5_5") (pintype "passive"))
    )
    (net (code "8") (name "GND") (class "Default")
      (node (ref "C1") (pin "1") (pinfunction "1_1") (pintype "passive"))
      (node (ref "C10") (pin "2") (pinfunction "2_2") (pintype "passive"))
      (node (ref "C11") (pin "2") (pinfunction "2_2") (pintype "passive"))
      (node (ref "C12") (pin "2") (pinfunction "2_2") (pintype "passive"))
      (node (ref "C13") (pin "2") (pinfunction "2_2") (pintype "passive"))
      (node (ref "C14") (pin "2") (pinfunction "2_2") (pintype "passive"))
      (node (ref "C15") (pin "2") (pinfunction "2_2") (pintype "passive"))
      (node (ref "C16") (pin "2") (pinfunction "2_2") (pintype "passive"))
      (node (ref "C17") (pin "2") (pinfunction "2_2") (pintype "passive"))
      (node (ref "C18") (pin "2") (pinfunction "2_2") (pintype "passive"))
      (node (ref "C19") (pin "2") (pinfunction "2_2") (pintype "passive"))
      (node (ref "C2") (pin "2") (pinfunction "2_2") (pintype "passive"))
      (node (ref "C20") (pin "2") (pinfunction "2_2") (pintype "passive"))
      (node (ref "C21") (pin "2") (pinfunction "2_2") (pintype "passive"))
      (node (ref "C22") (pin "2") (pinfunction "2_2") (pintype "passive"))
      (node (ref "C23") (pin "2") (pinfunction "2_2") (pintype "passive"))
      (node (ref "C24") (pin "2") (pinfunction "2_2") (pintype "passive"))
      (node (ref "C25") (pin "1") (pinfunction "1_1") (pintype "passive"))
      (node (ref "C26") (pin "1") (pinfunction "1_1") (pintype "passive"))
      (node (ref "C27") (pin "2") (pinfunction "2_2") (pintype "passive"))
      (node (ref "C28") (pin "2") (pinfunction "2_2") (pintype "passive"))
      (node (ref "C29") (pin "1") (pinfunction "1_1") (pintype "passive"))
      (node (ref "C3") (pin "1") (pinfunction "1_1") (pintype "passive"))
      (node (ref "C30") (pin "1") (pinfunction "1_1") (pintype "passive"))
      (node (ref "C31") (pin "2") (pinfunction "2_2") (pintype "passive"))
      (node (ref "C4") (pin "2") (pinfunction "2_2") (pintype "passive"))
      (node (ref "C5") (pin "2") (pinfunction "2_2") (pintype "passive"))
      (node (ref "C6") (pin "2") (pinfunction "2_2") (pintype "passive"))
      (node (ref "C7") (pin "2") (pinfunction "2_2") (pintype "passive"))
      (node (ref "C8") (pin "2") (pinfunction "2_2") (pintype "passive"))
      (node (ref "C9") (pin "2") (pinfunction "2_2") (pintype "passive"))
      (node (ref "DA1") (pin "1") (pinfunction "Gnd_1") (pintype "passive"))
      (node (ref "DA2") (pin "1") (pinfunction "Gnd_1") (pintype "passive"))
      (node (ref "DD1") (pin "101") (pinfunction "GND_101") (pintype "power_in"))
      (node (ref "DD1") (pin "116") (pinfunction "GND_116") (pintype "power_in"))
      (node (ref "DD1") (pin "118") (pinfunction "GND_118") (pintype "power_in"))
      (node (ref "DD1") (pin "127") (pinfunction "GND_127") (pintype "power_in"))
      (node (ref "DD1") (pin "136") (pinfunction "GND_136") (pintype "power_in"))
      (node (ref "DD1") (pin "138") (pinfunction "GND_138") (pintype "power_in"))
      (node (ref "DD1") (pin "18") (pinfunction "GNDA_PLL1_18") (pintype "power_in"))
      (node (ref "DD1") (pin "19") (pinfunction "GNDG_PLL1_19") (pintype "power_in"))
      (node (ref "DD1") (pin "22") (pinfunction "MSEL0_22") (pintype "input"))
      (node (ref "DD1") (pin "23") (pinfunction "MSEL1_23") (pintype "input"))
      (node (ref "DD1") (pin "30") (pinfunction "GND_30") (pintype "power_in"))
      (node (ref "DD1") (pin "43") (pinfunction "GND_43") (pintype "power_in"))
      (node (ref "DD1") (pin "45") (pinfunction "GND_45") (pintype "power_in"))
      (node (ref "DD1") (pin "54") (pinfunction "GND_54") (pintype "power_in"))
      (node (ref "DD1") (pin "63") (pinfunction "GND_63") (pintype "power_in"))
      (node (ref "DD1") (pin "65") (pinfunction "GND_65") (pintype "power_in"))
      (node (ref "DD1") (pin "80") (pinfunction "GND_80") (pintype "power_in"))
      (node (ref "DD1") (pin "9") (pinfunction "GND_9") (pintype "power_in"))
      (node (ref "DD1") (pin "91") (pinfunction "GNDG_PLL2_91") (pintype "power_in"))
      (node (ref "DS1") (pin "4") (pinfunction "GND_4") (pintype "power_in"))
      (node (ref "HL1") (pin "K") (pinfunction "K_K") (pintype "passive"))
      (node (ref "HL2") (pin "K") (pinfunction "K_K") (pintype "passive"))
      (node (ref "Q1") (pin "2") (pinfunction "Gnd_2") (pintype "passive"))
      (node (ref "R54") (pin "2") (pinfunction "2_2") (pintype "passive"))
      (node (ref "R8") (pin "2") (pinfunction "2_2") (pintype "passive"))
      (node (ref "XP1") (pin "10") (pinfunction "10_10") (pintype "passive"))
      (node (ref "XP1") (pin "2") (pinfunction "2_2") (pintype "passive"))
      (node (ref "XP2") (pin "10") (pinfunction "10_10") (pintype "passive"))
      (node (ref "XP2") (pin "2") (pinfunction "2_2") (pintype "passive"))
      (node (ref "XS1") (pin "5") (pinfunction "5_5") (pintype "passive"))
    )
    (net (code "9") (name "Net-(DA1-Vin)") (class "Default")
      (node (ref "C23") (pin "1") (pinfunction "1_1") (pintype "passive"))
      (node (ref "C24") (pin "1") (pinfunction "1_1") (pintype "passive"))
      (node (ref "C25") (pin "2") (pinfunction "2_2") (pintype "passive"))
      (node (ref "C26") (pin "2") (pinfunction "2_2") (pintype "passive"))
      (node (ref "DA1") (pin "3") (pinfunction "Vin_3") (pintype "passive"))
      (node (ref "DA2") (pin "3") (pinfunction "Vin_3") (pintype "passive"))
      (node (ref "ZL3") (pin "2") (pinfunction "2_2") (pintype "passive"))
    )
    (net (code "10") (name "Net-(DD1-CLK1,_LVDSCLK1n)") (class "Default")
      (node (ref "DD1") (pin "17") (pinfunction "CLK1,_LVDSCLK1n_17") (pintype "input"))
      (node (ref "R5") (pin "2") (pinfunction "2_2") (pintype "passive"))
    )
    (net (code "11") (name "Net-(DD1-CLK2,_LVDSCLK2p)") (class "Default")
      (node (ref "DD1") (pin "93") (pinfunction "CLK2,_LVDSCLK2p_93") (pintype "input"))
      (node (ref "R6") (pin "2") (pinfunction "2_2") (pintype "passive"))
    )
    (net (code "12") (name "Net-(DD1-CLK3,_LVDSCLK2n)") (class "Default")
      (node (ref "DD1") (pin "92") (pinfunction "CLK3,_LVDSCLK2n_92") (pintype "input"))
      (node (ref "R7") (pin "2") (pinfunction "2_2") (pintype "passive"))
    )
    (net (code "13") (name "Net-(DD1-DATA0)") (class "Default")
      (node (ref "DD1") (pin "13") (pinfunction "DATA0_13") (pintype "input"))
      (node (ref "DS1") (pin "2") (pinfunction "DATA_2") (pintype "output"))
      (node (ref "XP1") (pin "7") (pinfunction "7_7") (pintype "passive"))
    )
    (net (code "14") (name "Net-(DD1-DCLK)") (class "Default")
      (node (ref "DD1") (pin "24") (pinfunction "DCLK_24") (pintype "bidirectional"))
      (node (ref "DS1") (pin "6") (pinfunction "DCLK_6") (pintype "input"))
      (node (ref "XP1") (pin "1") (pinfunction "1_1") (pintype "passive"))
    )
    (net (code "15") (name "Net-(DD1-IO,_DPCLK0_(DQS1L))") (class "Default")
      (node (ref "DD1") (pin "28") (pinfunction "IO,_DPCLK0_(DQS1L)_28") (pintype "bidirectional"))
      (node (ref "R15") (pin "2") (pinfunction "2_2") (pintype "passive"))
    )
    (net (code "16") (name "Net-(DD1-IO,_DPCLK1)") (class "Default")
      (node (ref "DD1") (pin "10") (pinfunction "IO,_DPCLK1_10") (pintype "bidirectional"))
      (node (ref "R19") (pin "2") (pinfunction "2_2") (pintype "passive"))
    )
    (net (code "17") (name "Net-(DD1-IO,_DPCLK2_(DQS1T))") (class "Default")
      (node (ref "DD1") (pin "134") (pinfunction "IO,_DPCLK2_(DQS1T)_134") (pintype "bidirectional"))
      (node (ref "R33") (pin "2") (pinfunction "2_2") (pintype "passive"))
    )
    (net (code "18") (name "Net-(DD1-IO,_DPCLK3_(DQS0T))") (class "Default")
      (node (ref "DD1") (pin "119") (pinfunction "IO,_DPCLK3_(DQS0T)_119") (pintype "bidirectional"))
      (node (ref "R46") (pin "2") (pinfunction "2_2") (pintype "passive"))
    )
    (net (code "19") (name "Net-(DD1-IO,_DPCLK4_(DQS0R))") (class "Default")
      (node (ref "DD1") (pin "100") (pinfunction "IO,_DPCLK4_(DQS0R)_100") (pintype "bidirectional"))
      (node (ref "R61") (pin "1") (pinfunction "1_1") (pintype "passive"))
    )
    (net (code "20") (name "Net-(DD1-IO,_DPCLK5_(DQS1R))") (class "Default")
      (node (ref "DD1") (pin "82") (pinfunction "IO,_DPCLK5_(DQS1R)_82") (pintype "bidirectional"))
      (node (ref "R69") (pin "1") (pinfunction "1_1") (pintype "passive"))
    )
    (net (code "21") (name "Net-(DD1-IO,_DPCLK6_(DQS0B))") (class "Default")
      (node (ref "DD1") (pin "62") (pinfunction "IO,_DPCLK6_(DQS0B)_62") (pintype "bidirectional"))
      (node (ref "R83") (pin "1") (pinfunction "1_1") (pintype "passive"))
    )
    (net (code "22") (name "Net-(DD1-IO,_DPCLK7_(DQS1B))") (class "Default")
      (node (ref "DD1") (pin "47") (pinfunction "IO,_DPCLK7_(DQS1B)_47") (pintype "bidirectional"))
      (node (ref "R96") (pin "1") (pinfunction "1_1") (pintype "passive"))
    )
    (net (code "23") (name "Net-(DD1-IO,_LVDS0n)") (class "Default")
      (node (ref "DD1") (pin "36") (pinfunction "IO,_LVDS0n_36") (pintype "bidirectional"))
      (node (ref "R9") (pin "2") (pinfunction "2_2") (pintype "passive"))
    )
    (net (code "24") (name "Net-(DD1-IO,_LVDS0p_(DQ1L7))") (class "Default")
      (node (ref "DD1") (pin "35") (pinfunction "IO,_LVDS0p_(DQ1L7)_35") (pintype "bidirectional"))
      (node (ref "R10") (pin "2") (pinfunction "2_2") (pintype "passive"))
    )
    (net (code "25") (name "Net-(DD1-IO,_LVDS1n_(DQ1L6))") (class "Default")
      (node (ref "DD1") (pin "34") (pinfunction "IO,_LVDS1n_(DQ1L6)_34") (pintype "bidirectional"))
      (node (ref "R11") (pin "2") (pinfunction "2_2") (pintype "passive"))
    )
    (net (code "26") (name "Net-(DD1-IO,_LVDS1p_(DQ1L5))") (class "Default")
      (node (ref "DD1") (pin "33") (pinfunction "IO,_LVDS1p_(DQ1L5)_33") (pintype "bidirectional"))
      (node (ref "R12") (pin "2") (pinfunction "2_2") (pintype "passive"))
    )
    (net (code "27") (name "Net-(DD1-IO,_LVDS12p_(DQ1L3))") (class "Default")
      (node (ref "DD1") (pin "7") (pinfunction "IO,_LVDS12p_(DQ1L3)_7") (pintype "bidirectional"))
      (node (ref "R20") (pin "2") (pinfunction "2_2") (pintype "passive"))
    )
    (net (code "28") (name "Net-(DD1-IO,_LVDS13n)") (class "Default")
      (node (ref "DD1") (pin "4") (pinfunction "IO,_LVDS13n_4") (pintype "bidirectional"))
      (node (ref "R23") (pin "2") (pinfunction "2_2") (pintype "passive"))
    )
    (net (code "29") (name "Net-(DD1-IO,_LVDS13p_(CLKUSR){slash}(DQ1L1))") (class "Default")
      (node (ref "DD1") (pin "3") (pinfunction "IO,_LVDS13p_(CLKUSR)/(DQ1L1)_3") (pintype "bidirectional"))
      (node (ref "R24") (pin "2") (pinfunction "2_2") (pintype "passive"))
    )
    (net (code "30") (name "Net-(DD1-IO,_LVDS14n_(CRC_ERROR){slash}(DQ1L0))") (class "Default")
      (node (ref "DD1") (pin "2") (pinfunction "IO,_LVDS14n_(CRC_ERROR)/(DQ1L0)_2") (pintype "bidirectional"))
      (node (ref "R25") (pin "2") (pinfunction "2_2") (pintype "passive"))
    )
    (net (code "31") (name "Net-(DD1-IO,_LVDS14p_(INIT_DONE){slash}(DM1L))") (class "Default")
      (node (ref "DD1") (pin "1") (pinfunction "IO,_LVDS14p_(INIT_DONE)/(DM1L)_1") (pintype "bidirectional"))
      (node (ref "R26") (pin "2") (pinfunction "2_2") (pintype "passive"))
    )
    (net (code "32") (name "Net-(DD1-IO,_LVDS15n_(DEV_OE))") (class "Default")
      (node (ref "DD1") (pin "143") (pinfunction "IO,_LVDS15n_(DEV_OE)_143") (pintype "bidirectional"))
      (node (ref "R28") (pin "2") (pinfunction "2_2") (pintype "passive"))
    )
    (net (code "33") (name "Net-(DD1-IO,_LVDS15p_(DEV_CLRn))") (class "Default")
      (node (ref "DD1") (pin "144") (pinfunction "IO,_LVDS15p_(DEV_CLRn)_144") (pintype "bidirectional"))
      (node (ref "R27") (pin "2") (pinfunction "2_2") (pintype "passive"))
    )
    (net (code "34") (name "Net-(DD1-IO,_LVDS17n_(DQ0T6))") (class "Default")
      (node (ref "DD1") (pin "141") (pinfunction "IO,_LVDS17n_(DQ0T6)_141") (pintype "bidirectional"))
      (node (ref "R30") (pin "2") (pinfunction "2_2") (pintype "passive"))
    )
    (net (code "35") (name "Net-(DD1-IO,_LVDS17p_(DQ0T7))") (class "Default")
      (node (ref "DD1") (pin "142") (pinfunction "IO,_LVDS17p_(DQ0T7)_142") (pintype "bidirectional"))
      (node (ref "R29") (pin "2") (pinfunction "2_2") (pintype "passive"))
    )
    (net (code "36") (name "Net-(DD1-IO,_LVDS18n_(DQ0T4))") (class "Default")
      (node (ref "DD1") (pin "139") (pinfunction "IO,_LVDS18n_(DQ0T4)_139") (pintype "bidirectional"))
      (node (ref "R32") (pin "2") (pinfunction "2_2") (pintype "passive"))
    )
    (net (code "37") (name "Net-(DD1-IO,_LVDS18p_(DQ0T5))") (class "Default")
      (node (ref "DD1") (pin "140") (pinfunction "IO,_LVDS18p_(DQ0T5)_140") (pintype "bidirectional"))
      (node (ref "R31") (pin "2") (pinfunction "2_2") (pintype "passive"))
    )
    (net (code "38") (name "Net-(DD1-IO,_LVDS19p)") (class "Default")
      (node (ref "DD1") (pin "132") (pinfunction "IO,_LVDS19p_132") (pintype "bidirectional"))
      (node (ref "R35") (pin "2") (pinfunction "2_2") (pintype "passive"))
    )
    (net (code "39") (name "Net-(DD1-IO,_LVDS23n)") (class "Default")
      (node (ref "DD1") (pin "130") (pinfunction "IO,_LVDS23n_130") (pintype "bidirectional"))
      (node (ref "R37") (pin "2") (pinfunction "2_2") (pintype "passive"))
    )
    (net (code "40") (name "Net-(DD1-IO,_LVDS23p)") (class "Default")
      (node (ref "DD1") (pin "131") (pinfunction "IO,_LVDS23p_131") (pintype "bidirectional"))
      (node (ref "R36") (pin "2") (pinfunction "2_2") (pintype "passive"))
    )
    (net (code "41") (name "Net-(DD1-IO,_LVDS24n)") (class "Default")
      (node (ref "DD1") (pin "128") (pinfunction "IO,_LVDS24n_128") (pintype "bidirectional"))
      (node (ref "R39") (pin "2") (pinfunction "2_2") (pintype "passive"))
    )
    (net (code "42") (name "Net-(DD1-IO,_LVDS24p)") (class "Default")
      (node (ref "DD1") (pin "129") (pinfunction "IO,_LVDS24p_129") (pintype "bidirectional"))
      (node (ref "R38") (pin "2") (pinfunction "2_2") (pintype "passive"))
    )
    (net (code "43") (name "Net-(DD1-IO,_LVDS25n_(DM0T))") (class "Default")
      (node (ref "DD1") (pin "123") (pinfunction "IO,_LVDS25n_(DM0T)_123") (pintype "bidirectional"))
      (node (ref "R42") (pin "2") (pinfunction "2_2") (pintype "passive"))
    )
    (net (code "44") (name "Net-(DD1-IO,_LVDS25p)") (class "Default")
      (node (ref "DD1") (pin "124") (pinfunction "IO,_LVDS25p_124") (pintype "bidirectional"))
      (node (ref "R41") (pin "2") (pinfunction "2_2") (pintype "passive"))
    )
    (net (code "45") (name "Net-(DD1-IO,_LVDS27n)") (class "Default")
      (node (ref "DD1") (pin "122") (pinfunction "IO,_LVDS27n_122") (pintype "bidirectional"))
      (node (ref "R43") (pin "2") (pinfunction "2_2") (pintype "passive"))
    )
    (net (code "46") (name "Net-(DD1-IO,_LVDS31n_(DQ0T2))") (class "Default")
      (node (ref "DD1") (pin "113") (pinfunction "IO,_LVDS31n_(DQ0T2)_113") (pintype "bidirectional"))
      (node (ref "R48") (pin "2") (pinfunction "2_2") (pintype "passive"))
    )
    (net (code "47") (name "Net-(DD1-IO,_LVDS31p_(DQ0T3))") (class "Default")
      (node (ref "DD1") (pin "114") (pinfunction "IO,_LVDS31p_(DQ0T3)_114") (pintype "bidirectional"))
      (node (ref "R47") (pin "2") (pinfunction "2_2") (pintype "passive"))
    )
    (net (code "48") (name "Net-(DD1-IO,_LVDS32n_(DQ0T0))") (class "Default")
      (node (ref "DD1") (pin "111") (pinfunction "IO,_LVDS32n_(DQ0T0)_111") (pintype "bidirectional"))
      (node (ref "R50") (pin "2") (pinfunction "2_2") (pintype "passive"))
    )
    (net (code "49") (name "Net-(DD1-IO,_LVDS32p_(DQ0T1))") (class "Default")
      (node (ref "DD1") (pin "112") (pinfunction "IO,_LVDS32p_(DQ0T1)_112") (pintype "bidirectional"))
      (node (ref "R49") (pin "2") (pinfunction "2_2") (pintype "passive"))
    )
    (net (code "50") (name "Net-(DD1-IO,_LVDS34n)") (class "Default")
      (node (ref "DD1") (pin "109") (pinfunction "IO,_LVDS34n_109") (pintype "bidirectional"))
      (node (ref "R52") (pin "2") (pinfunction "2_2") (pintype "passive"))
    )
    (net (code "51") (name "Net-(DD1-IO,_LVDS34p)") (class "Default")
      (node (ref "DD1") (pin "110") (pinfunction "IO,_LVDS34p_110") (pintype "bidirectional"))
      (node (ref "R51") (pin "2") (pinfunction "2_2") (pintype "passive"))
    )
    (net (code "52") (name "Net-(DD1-IO,_LVDS35n)") (class "Default")
      (node (ref "DD1") (pin "107") (pinfunction "IO,_LVDS35n_107") (pintype "bidirectional"))
      (node (ref "R56") (pin "1") (pinfunction "1_1") (pintype "passive"))
    )
    (net (code "53") (name "Net-(DD1-IO,_LVDS35p)") (class "Default")
      (node (ref "DD1") (pin "108") (pinfunction "IO,_LVDS35p_108") (pintype "bidirectional"))
      (node (ref "R55") (pin "1") (pinfunction "1_1") (pintype "passive"))
    )
    (net (code "54") (name "Net-(DD1-IO,_LVDS36n)") (class "Default")
      (node (ref "DD1") (pin "105") (pinfunction "IO,_LVDS36n_105") (pintype "bidirectional"))
      (node (ref "R58") (pin "1") (pinfunction "1_1") (pintype "passive"))
    )
    (net (code "55") (name "Net-(DD1-IO,_LVDS36p)") (class "Default")
      (node (ref "DD1") (pin "106") (pinfunction "IO,_LVDS36p_106") (pintype "bidirectional"))
      (node (ref "R57") (pin "1") (pinfunction "1_1") (pintype "passive"))
    )
    (net (code "56") (name "Net-(DD1-IO,_LVDS38n_(DQ1R2))") (class "Default")
      (node (ref "DD1") (pin "98") (pinfunction "IO,_LVDS38n_(DQ1R2)_98") (pintype "bidirectional"))
      (node (ref "R63") (pin "1") (pinfunction "1_1") (pintype "passive"))
    )
    (net (code "57") (name "Net-(DD1-IO,_LVDS38p_(DQ1R1))") (class "Default")
      (node (ref "DD1") (pin "99") (pinfunction "IO,_LVDS38p_(DQ1R1)_99") (pintype "bidirectional"))
      (node (ref "R62") (pin "1") (pinfunction "1_1") (pintype "passive"))
    )
    (net (code "58") (name "Net-(DD1-IO,_LVDS39p_(DQ1R3))") (class "Default")
      (node (ref "DD1") (pin "97") (pinfunction "IO,_LVDS39p_(DQ1R3)_97") (pintype "bidirectional"))
      (node (ref "R64") (pin "1") (pinfunction "1_1") (pintype "passive"))
    )
    (net (code "59") (name "Net-(DD1-IO,_LVDS47n_(DM1R))") (class "Default")
      (node (ref "DD1") (pin "85") (pinfunction "IO,_LVDS47n_(DM1R)_85") (pintype "bidirectional"))
      (node (ref "R66") (pin "1") (pinfunction "1_1") (pintype "passive"))
    )
    (net (code "60") (name "Net-(DD1-IO,_LVDS48n_(DQ1R5))") (class "Default")
      (node (ref "DD1") (pin "83") (pinfunction "IO,_LVDS48n_(DQ1R5)_83") (pintype "bidirectional"))
      (node (ref "R68") (pin "1") (pinfunction "1_1") (pintype "passive"))
    )
    (net (code "61") (name "Net-(DD1-IO,_LVDS48p_(DQ1R4))") (class "Default")
      (node (ref "DD1") (pin "84") (pinfunction "IO,_LVDS48p_(DQ1R4)_84") (pintype "bidirectional"))
      (node (ref "R67") (pin "1") (pinfunction "1_1") (pintype "passive"))
    )
    (net (code "62") (name "Net-(DD1-IO,_LVDS49n_(DQ1R7))") (class "Default")
      (node (ref "DD1") (pin "77") (pinfunction "IO,_LVDS49n_(DQ1R7)_77") (pintype "bidirectional"))
      (node (ref "R72") (pin "1") (pinfunction "1_1") (pintype "passive"))
    )
    (net (code "63") (name "Net-(DD1-IO,_LVDS49p_(DQ1R6))") (class "Default")
      (node (ref "DD1") (pin "78") (pinfunction "IO,_LVDS49p_(DQ1R6)_78") (pintype "bidirectional"))
      (node (ref "R71") (pin "1") (pinfunction "1_1") (pintype "passive"))
    )
    (net (code "64") (name "Net-(DD1-IO,_LVDS50n)") (class "Default")
      (node (ref "DD1") (pin "75") (pinfunction "IO,_LVDS50n_75") (pintype "bidirectional"))
      (node (ref "R74") (pin "1") (pinfunction "1_1") (pintype "passive"))
    )
    (net (code "65") (name "Net-(DD1-IO,_LVDS50p)") (class "Default")
      (node (ref "DD1") (pin "76") (pinfunction "IO,_LVDS50p_76") (pintype "bidirectional"))
      (node (ref "R73") (pin "1") (pinfunction "1_1") (pintype "passive"))
    )
    (net (code "66") (name "Net-(DD1-IO,_LVDS51n)") (class "Default")
      (node (ref "DD1") (pin "73") (pinfunction "IO,_LVDS51n_73") (pintype "bidirectional"))
      (node (ref "R76") (pin "1") (pinfunction "1_1") (pintype "passive"))
    )
    (net (code "67") (name "Net-(DD1-IO,_LVDS51p)") (class "Default")
      (node (ref "DD1") (pin "74") (pinfunction "IO,_LVDS51p_74") (pintype "bidirectional"))
      (node (ref "R75") (pin "1") (pinfunction "1_1") (pintype "passive"))
    )
    (net (code "68") (name "Net-(DD1-IO,_LVDS52n)") (class "Default")
      (node (ref "DD1") (pin "72") (pinfunction "IO,_LVDS52n_72") (pintype "bidirectional"))
      (node (ref "R77") (pin "1") (pinfunction "1_1") (pintype "passive"))
    )
    (net (code "69") (name "Net-(DD1-IO,_LVDS52p)") (class "Default")
      (node (ref "DD1") (pin "71") (pinfunction "IO,_LVDS52p_71") (pintype "bidirectional"))
      (node (ref "R78") (pin "1") (pinfunction "1_1") (pintype "passive"))
    )
    (net (code "70") (name "Net-(DD1-IO,_LVDS54n_(DQ1B0))") (class "Default")
      (node (ref "DD1") (pin "70") (pinfunction "IO,_LVDS54n_(DQ1B0)_70") (pintype "bidirectional"))
      (node (ref "R79") (pin "1") (pinfunction "1_1") (pintype "passive"))
    )
    (net (code "71") (name "Net-(DD1-IO,_LVDS54p_(DQ1B1))") (class "Default")
      (node (ref "DD1") (pin "69") (pinfunction "IO,_LVDS54p_(DQ1B1)_69") (pintype "bidirectional"))
      (node (ref "R80") (pin "1") (pinfunction "1_1") (pintype "passive"))
    )
    (net (code "72") (name "Net-(DD1-IO,_LVDS55n_(DQ1B2))") (class "Default")
      (node (ref "DD1") (pin "68") (pinfunction "IO,_LVDS55n_(DQ1B2)_68") (pintype "bidirectional"))
      (node (ref "R81") (pin "1") (pinfunction "1_1") (pintype "passive"))
    )
    (net (code "73") (name "Net-(DD1-IO,_LVDS55p_(DQ1B3))") (class "Default")
      (node (ref "DD1") (pin "67") (pinfunction "IO,_LVDS55p_(DQ1B3)_67") (pintype "bidirectional"))
      (node (ref "R82") (pin "1") (pinfunction "1_1") (pintype "passive"))
    )
    (net (code "74") (name "Net-(DD1-IO,_LVDS59n)") (class "Default")
      (node (ref "DD1") (pin "59") (pinfunction "IO,_LVDS59n_59") (pintype "bidirectional"))
      (node (ref "R86") (pin "1") (pinfunction "1_1") (pintype "passive"))
    )
    (net (code "75") (name "Net-(DD1-IO,_LVDS61n)") (class "Default")
      (node (ref "DD1") (pin "58") (pinfunction "IO,_LVDS61n_58") (pintype "bidirectional"))
      (node (ref "R87") (pin "1") (pinfunction "1_1") (pintype "passive"))
    )
    (net (code "76") (name "Net-(DD1-IO,_LVDS61p_(DM1B))") (class "Default")
      (node (ref "DD1") (pin "57") (pinfunction "IO,_LVDS61p_(DM1B)_57") (pintype "bidirectional"))
      (node (ref "R88") (pin "1") (pinfunction "1_1") (pintype "passive"))
    )
    (net (code "77") (name "Net-(DD1-IO,_LVDS62n)") (class "Default")
      (node (ref "DD1") (pin "53") (pinfunction "IO,_LVDS62n_53") (pintype "bidirectional"))
      (node (ref "R90") (pin "1") (pinfunction "1_1") (pintype "passive"))
    )
    (net (code "78") (name "Net-(DD1-IO,_LVDS62p)") (class "Default")
      (node (ref "DD1") (pin "52") (pinfunction "IO,_LVDS62p_52") (pintype "bidirectional"))
      (node (ref "R91") (pin "1") (pinfunction "1_1") (pintype "passive"))
    )
    (net (code "79") (name "Net-(DD1-IO,_LVDS63n)") (class "Default")
      (node (ref "DD1") (pin "51") (pinfunction "IO,_LVDS63n_51") (pintype "bidirectional"))
      (node (ref "R92") (pin "1") (pinfunction "1_1") (pintype "passive"))
    )
    (net (code "80") (name "Net-(DD1-IO,_LVDS63p)") (class "Default")
      (node (ref "DD1") (pin "50") (pinfunction "IO,_LVDS63p_50") (pintype "bidirectional"))
      (node (ref "R93") (pin "1") (pinfunction "1_1") (pintype "passive"))
    )
    (net (code "81") (name "Net-(DD1-IO,_LVDS67p)") (class "Default")
      (node (ref "DD1") (pin "49") (pinfunction "IO,_LVDS67p_49") (pintype "bidirectional"))
      (node (ref "R94") (pin "1") (pinfunction "1_1") (pintype "passive"))
    )
    (net (code "82") (name "Net-(DD1-IO,_LVDS68n_(DQ1B4))") (class "Default")
      (node (ref "DD1") (pin "42") (pinfunction "IO,_LVDS68n_(DQ1B4)_42") (pintype "bidirectional"))
      (node (ref "R97") (pin "1") (pinfunction "1_1") (pintype "passive"))
    )
    (net (code "83") (name "Net-(DD1-IO,_LVDS68p_(DQ1B5))") (class "Default")
      (node (ref "DD1") (pin "41") (pinfunction "IO,_LVDS68p_(DQ1B5)_41") (pintype "bidirectional"))
      (node (ref "R98") (pin "1") (pinfunction "1_1") (pintype "passive"))
    )
    (net (code "84") (name "Net-(DD1-IO,_LVDS69n_(DQ1B6))") (class "Default")
      (node (ref "DD1") (pin "40") (pinfunction "IO,_LVDS69n_(DQ1B6)_40") (pintype "bidirectional"))
      (node (ref "R99") (pin "1") (pinfunction "1_1") (pintype "passive"))
    )
    (net (code "85") (name "Net-(DD1-IO,_LVDS69p_(DQ1B7))") (class "Default")
      (node (ref "DD1") (pin "39") (pinfunction "IO,_LVDS69p_(DQ1B7)_39") (pintype "bidirectional"))
      (node (ref "R100") (pin "1") (pinfunction "1_1") (pintype "passive"))
    )
    (net (code "86") (name "Net-(DD1-IO,_LVDS71n)") (class "Default")
      (node (ref "DD1") (pin "38") (pinfunction "IO,_LVDS71n_38") (pintype "bidirectional"))
      (node (ref "R101") (pin "1") (pinfunction "1_1") (pintype "passive"))
    )
    (net (code "87") (name "Net-(DD1-IO,_LVDS71p)") (class "Default")
      (node (ref "DD1") (pin "37") (pinfunction "IO,_LVDS71p_37") (pintype "bidirectional"))
      (node (ref "R102") (pin "1") (pinfunction "1_1") (pintype "passive"))
    )
    (net (code "88") (name "Net-(DD1-IO,_PLL1_OUTn)") (class "Default")
      (node (ref "DD1") (pin "27") (pinfunction "IO,_PLL1_OUTn_27") (pintype "bidirectional"))
      (node (ref "R16") (pin "2") (pinfunction "2_2") (pintype "passive"))
    )
    (net (code "89") (name "Net-(DD1-IO,_PLL1_OUTp)") (class "Default")
      (node (ref "DD1") (pin "26") (pinfunction "IO,_PLL1_OUTp_26") (pintype "bidirectional"))
      (node (ref "R17") (pin "2") (pinfunction "2_2") (pintype "passive"))
    )
    (net (code "90") (name "Net-(DD1-IO,_VREF0B1)") (class "Default")
      (node (ref "DD1") (pin "5") (pinfunction "IO,_VREF0B1_5") (pintype "bidirectional"))
      (node (ref "R22") (pin "2") (pinfunction "2_2") (pintype "passive"))
    )
    (net (code "91") (name "Net-(DD1-IO,_VREF0B2)") (class "Default")
      (node (ref "DD1") (pin "120") (pinfunction "IO,_VREF0B2_120") (pintype "bidirectional"))
      (node (ref "R45") (pin "2") (pinfunction "2_2") (pintype "passive"))
    )
    (net (code "92") (name "Net-(DD1-IO,_VREF0B3)") (class "Default")
      (node (ref "DD1") (pin "104") (pinfunction "IO,_VREF0B3_104") (pintype "bidirectional"))
      (node (ref "R59") (pin "1") (pinfunction "1_1") (pintype "passive"))
    )
    (net (code "93") (name "Net-(DD1-IO,_VREF0B4)") (class "Default")
      (node (ref "DD1") (pin "61") (pinfunction "IO,_VREF0B4_61") (pintype "bidirectional"))
      (node (ref "R84") (pin "1") (pinfunction "1_1") (pintype "passive"))
    )
    (net (code "94") (name "Net-(DD1-IO,_VREF1B1)") (class "Default")
      (node (ref "DD1") (pin "11") (pinfunction "IO,_VREF1B1_11") (pintype "bidirectional"))
      (node (ref "R18") (pin "2") (pinfunction "2_2") (pintype "passive"))
    )
    (net (code "95") (name "Net-(DD1-IO,_VREF1B2)") (class "Default")
      (node (ref "DD1") (pin "125") (pinfunction "IO,_VREF1B2_125") (pintype "bidirectional"))
      (node (ref "R40") (pin "2") (pinfunction "2_2") (pintype "passive"))
    )
    (net (code "96") (name "Net-(DD1-IO,_VREF1B3)") (class "Default")
      (node (ref "DD1") (pin "96") (pinfunction "IO,_VREF1B3_96") (pintype "bidirectional"))
      (node (ref "R65") (pin "1") (pinfunction "1_1") (pintype "passive"))
    )
    (net (code "97") (name "Net-(DD1-IO,_VREF1B4)") (class "Default")
      (node (ref "DD1") (pin "56") (pinfunction "IO,_VREF1B4_56") (pintype "bidirectional"))
      (node (ref "R89") (pin "1") (pinfunction "1_1") (pintype "passive"))
    )
    (net (code "98") (name "Net-(DD1-IO,_VREF2B1)") (class "Default")
      (node (ref "DD1") (pin "31") (pinfunction "IO,_VREF2B1_31") (pintype "bidirectional"))
      (node (ref "R14") (pin "2") (pinfunction "2_2") (pintype "passive"))
    )
    (net (code "99") (name "Net-(DD1-IO,_VREF2B2)") (class "Default")
      (node (ref "DD1") (pin "133") (pinfunction "IO,_VREF2B2_133") (pintype "bidirectional"))
      (node (ref "R34") (pin "2") (pinfunction "2_2") (pintype "passive"))
    )
    (net (code "100") (name "Net-(DD1-IO,_VREF2B3)") (class "Default")
      (node (ref "DD1") (pin "79") (pinfunction "IO,_VREF2B3_79") (pintype "bidirectional"))
      (node (ref "R70") (pin "1") (pinfunction "1_1") (pintype "passive"))
    )
    (net (code "101") (name "Net-(DD1-IO,_VREF2B4)") (class "Default")
      (node (ref "DD1") (pin "48") (pinfunction "IO,_VREF2B4_48") (pintype "bidirectional"))
      (node (ref "R95") (pin "1") (pinfunction "1_1") (pintype "passive"))
    )
    (net (code "102") (name "Net-(DD1-IO-Pad60)") (class "Default")
      (node (ref "DD1") (pin "60") (pinfunction "IO_60") (pintype "bidirectional"))
      (node (ref "R85") (pin "1") (pinfunction "1_1") (pintype "passive"))
    )
    (net (code "103") (name "Net-(DD1-IO-Pad121)") (class "Default")
      (node (ref "DD1") (pin "121") (pinfunction "IO_121") (pintype "bidirectional"))
      (node (ref "R44") (pin "2") (pinfunction "2_2") (pintype "passive"))
    )
    (net (code "104") (name "Net-(DD1-IO_(ASDO))") (class "Default")
      (node (ref "DD1") (pin "25") (pinfunction "IO_(ASDO)_25") (pintype "bidirectional"))
      (node (ref "DS1") (pin "5") (pinfunction "ASDI_5") (pintype "input"))
      (node (ref "XP1") (pin "9") (pinfunction "9_9") (pintype "passive"))
    )
    (net (code "105") (name "Net-(DD1-IO_(DQ1L2))") (class "Default")
      (node (ref "DD1") (pin "6") (pinfunction "IO_(DQ1L2)_6") (pintype "bidirectional"))
      (node (ref "R21") (pin "2") (pinfunction "2_2") (pintype "passive"))
    )
    (net (code "106") (name "Net-(DD1-IO_(DQ1L4))") (class "Default")
      (node (ref "DD1") (pin "32") (pinfunction "IO_(DQ1L4)_32") (pintype "bidirectional"))
      (node (ref "R13") (pin "2") (pinfunction "2_2") (pintype "passive"))
    )
    (net (code "107") (name "Net-(DD1-IO_(DQ1R0))") (class "Default")
      (node (ref "DD1") (pin "103") (pinfunction "IO_(DQ1R0)_103") (pintype "bidirectional"))
      (node (ref "R60") (pin "1") (pinfunction "1_1") (pintype "passive"))
    )
    (net (code "108") (name "Net-(DD1-IO_(nCSO))") (class "Default")
      (node (ref "DD1") (pin "12") (pinfunction "IO_(nCSO)_12") (pintype "bidirectional"))
      (node (ref "DS1") (pin "1") (pinfunction "nCS_1") (pintype "input"))
      (node (ref "XP1") (pin "8") (pinfunction "8_8") (pintype "passive"))
    )
    (net (code "109") (name "Net-(DD1-VCCA_PLL1)") (class "Default")
      (node (ref "C17") (pin "1") (pinfunction "1_1") (pintype "passive"))
      (node (ref "C21") (pin "1") (pinfunction "1_1") (pintype "passive"))
      (node (ref "DD1") (pin "15") (pinfunction "VCCA_PLL1_15") (pintype "power_in"))
      (node (ref "ZL1") (pin "2") (pinfunction "2_2") (pintype "passive"))
    )
    (net (code "110") (name "Net-(DD1-VCCA_PLL2)") (class "Default")
      (node (ref "C18") (pin "1") (pinfunction "1_1") (pintype "passive"))
      (node (ref "C22") (pin "1") (pinfunction "1_1") (pintype "passive"))
      (node (ref "DD1") (pin "94") (pinfunction "VCCA_PLL2_94") (pintype "power_in"))
      (node (ref "ZL2") (pin "2") (pinfunction "2_2") (pintype "passive"))
    )
    (net (code "111") (name "Net-(DD1-nCE)") (class "Default")
      (node (ref "DD1") (pin "21") (pinfunction "nCE_21") (pintype "input"))
      (node (ref "R8") (pin "1") (pinfunction "1_1") (pintype "passive"))
      (node (ref "XP1") (pin "6") (pinfunction "6_6") (pintype "passive"))
    )
    (net (code "112") (name "Net-(DD1-nCONFIG)") (class "Default")
      (node (ref "DD1") (pin "14") (pinfunction "nCONFIG_14") (pintype "input"))
      (node (ref "R3") (pin "1") (pinfunction "1_1") (pintype "passive"))
      (node (ref "XP1") (pin "5") (pinfunction "5_5") (pintype "passive"))
    )
    (net (code "113") (name "Net-(DD1-nSTATUS)") (class "Default")
      (node (ref "DD1") (pin "87") (pinfunction "nSTATUS_87") (pintype "bidirectional"))
      (node (ref "R53") (pin "1") (pinfunction "1_1") (pintype "passive"))
    )
    (net (code "114") (name "Net-(HL1-PadA)") (class "Default")
      (node (ref "HL1") (pin "A") (pinfunction "A_A") (pintype "passive"))
      (node (ref "R76") (pin "2") (pinfunction "2_2") (pintype "passive"))
      (node (ref "XP65") (pin "1") (pinfunction "1_1") (pintype "passive"))
    )
    (net (code "115") (name "Net-(HL2-PadA)") (class "Default")
      (node (ref "HL2") (pin "A") (pinfunction "A_A") (pintype "passive"))
      (node (ref "R77") (pin "2") (pinfunction "2_2") (pintype "passive"))
      (node (ref "XP66") (pin "1") (pinfunction "1_1") (pintype "passive"))
    )
    (net (code "116") (name "Net-(Q1-OE)") (class "Default")
      (node (ref "Q1") (pin "1") (pinfunction "OE_1") (pintype "passive"))
      (node (ref "R1") (pin "2") (pinfunction "2_2") (pintype "passive"))
    )
    (net (code "117") (name "Net-(Q1-Out)") (class "Default")
      (node (ref "Q1") (pin "3") (pinfunction "Out_3") (pintype "passive"))
      (node (ref "R4") (pin "1") (pinfunction "1_1") (pintype "passive"))
      (node (ref "R5") (pin "1") (pinfunction "1_1") (pintype "passive"))
      (node (ref "XP94") (pin "1") (pinfunction "1_1") (pintype "passive"))
      (node (ref "XP95") (pin "1") (pinfunction "1_1") (pintype "passive"))
    )
    (net (code "118") (name "Net-(R6-Pad1)") (class "Default")
      (node (ref "R6") (pin "1") (pinfunction "1_1") (pintype "passive"))
      (node (ref "XP96") (pin "1") (pinfunction "1_1") (pintype "passive"))
    )
    (net (code "119") (name "Net-(R7-Pad1)") (class "Default")
      (node (ref "R7") (pin "1") (pinfunction "1_1") (pintype "passive"))
      (node (ref "XP97") (pin "1") (pinfunction "1_1") (pintype "passive"))
    )
    (net (code "120") (name "Net-(R9-Pad1)") (class "Default")
      (node (ref "R9") (pin "1") (pinfunction "1_1") (pintype "passive"))
      (node (ref "XP3") (pin "1") (pinfunction "1_1") (pintype "passive"))
    )
    (net (code "121") (name "Net-(R10-Pad1)") (class "Default")
      (node (ref "R10") (pin "1") (pinfunction "1_1") (pintype "passive"))
      (node (ref "XP4") (pin "1") (pinfunction "1_1") (pintype "passive"))
    )
    (net (code "122") (name "Net-(R11-Pad1)") (class "Default")
      (node (ref "R11") (pin "1") (pinfunction "1_1") (pintype "passive"))
      (node (ref "XP5") (pin "1") (pinfunction "1_1") (pintype "passive"))
    )
    (net (code "123") (name "Net-(R12-Pad1)") (class "Default")
      (node (ref "R12") (pin "1") (pinfunction "1_1") (pintype "passive"))
      (node (ref "XP6") (pin "1") (pinfunction "1_1") (pintype "passive"))
    )
    (net (code "124") (name "Net-(R13-Pad1)") (class "Default")
      (node (ref "R13") (pin "1") (pinfunction "1_1") (pintype "passive"))
      (node (ref "XP7") (pin "1") (pinfunction "1_1") (pintype "passive"))
    )
    (net (code "125") (name "Net-(R14-Pad1)") (class "Default")
      (node (ref "R14") (pin "1") (pinfunction "1_1") (pintype "passive"))
      (node (ref "XP8") (pin "1") (pinfunction "1_1") (pintype "passive"))
    )
    (net (code "126") (name "Net-(R15-Pad1)") (class "Default")
      (node (ref "R15") (pin "1") (pinfunction "1_1") (pintype "passive"))
      (node (ref "XP9") (pin "1") (pinfunction "1_1") (pintype "passive"))
    )
    (net (code "127") (name "Net-(R16-Pad1)") (class "Default")
      (node (ref "R16") (pin "1") (pinfunction "1_1") (pintype "passive"))
      (node (ref "XP10") (pin "1") (pinfunction "1_1") (pintype "passive"))
    )
    (net (code "128") (name "Net-(R17-Pad1)") (class "Default")
      (node (ref "R17") (pin "1") (pinfunction "1_1") (pintype "passive"))
      (node (ref "XP11") (pin "1") (pinfunction "1_1") (pintype "passive"))
    )
    (net (code "129") (name "Net-(R18-Pad1)") (class "Default")
      (node (ref "R18") (pin "1") (pinfunction "1_1") (pintype "passive"))
      (node (ref "XP12") (pin "1") (pinfunction "1_1") (pintype "passive"))
    )
    (net (code "130") (name "Net-(R19-Pad1)") (class "Default")
      (node (ref "R19") (pin "1") (pinfunction "1_1") (pintype "passive"))
      (node (ref "XP13") (pin "1") (pinfunction "1_1") (pintype "passive"))
    )
    (net (code "131") (name "Net-(R20-Pad1)") (class "Default")
      (node (ref "R20") (pin "1") (pinfunction "1_1") (pintype "passive"))
      (node (ref "XP14") (pin "1") (pinfunction "1_1") (pintype "passive"))
    )
    (net (code "132") (name "Net-(R21-Pad1)") (class "Default")
      (node (ref "R21") (pin "1") (pinfunction "1_1") (pintype "passive"))
      (node (ref "XP15") (pin "1") (pinfunction "1_1") (pintype "passive"))
    )
    (net (code "133") (name "Net-(R22-Pad1)") (class "Default")
      (node (ref "R22") (pin "1") (pinfunction "1_1") (pintype "passive"))
      (node (ref "XP16") (pin "1") (pinfunction "1_1") (pintype "passive"))
    )
    (net (code "134") (name "Net-(R23-Pad1)") (class "Default")
      (node (ref "R23") (pin "1") (pinfunction "1_1") (pintype "passive"))
      (node (ref "XP17") (pin "1") (pinfunction "1_1") (pintype "passive"))
    )
    (net (code "135") (name "Net-(R24-Pad1)") (class "Default")
      (node (ref "R24") (pin "1") (pinfunction "1_1") (pintype "passive"))
      (node (ref "XP18") (pin "1") (pinfunction "1_1") (pintype "passive"))
    )
    (net (code "136") (name "Net-(R25-Pad1)") (class "Default")
      (node (ref "R25") (pin "1") (pinfunction "1_1") (pintype "passive"))
      (node (ref "XP19") (pin "1") (pinfunction "1_1") (pintype "passive"))
    )
    (net (code "137") (name "Net-(R26-Pad1)") (class "Default")
      (node (ref "R26") (pin "1") (pinfunction "1_1") (pintype "passive"))
      (node (ref "XP20") (pin "1") (pinfunction "1_1") (pintype "passive"))
    )
    (net (code "138") (name "Net-(R27-Pad1)") (class "Default")
      (node (ref "R27") (pin "1") (pinfunction "1_1") (pintype "passive"))
      (node (ref "XP21") (pin "1") (pinfunction "1_1") (pintype "passive"))
    )
    (net (code "139") (name "Net-(R28-Pad1)") (class "Default")
      (node (ref "R28") (pin "1") (pinfunction "1_1") (pintype "passive"))
      (node (ref "XP22") (pin "1") (pinfunction "1_1") (pintype "passive"))
    )
    (net (code "140") (name "Net-(R29-Pad1)") (class "Default")
      (node (ref "R29") (pin "1") (pinfunction "1_1") (pintype "passive"))
      (node (ref "XP23") (pin "1") (pinfunction "1_1") (pintype "passive"))
    )
    (net (code "141") (name "Net-(R30-Pad1)") (class "Default")
      (node (ref "R30") (pin "1") (pinfunction "1_1") (pintype "passive"))
      (node (ref "XP24") (pin "1") (pinfunction "1_1") (pintype "passive"))
    )
    (net (code "142") (name "Net-(R31-Pad1)") (class "Default")
      (node (ref "R31") (pin "1") (pinfunction "1_1") (pintype "passive"))
      (node (ref "XP25") (pin "1") (pinfunction "1_1") (pintype "passive"))
    )
    (net (code "143") (name "Net-(R32-Pad1)") (class "Default")
      (node (ref "R32") (pin "1") (pinfunction "1_1") (pintype "passive"))
      (node (ref "XP26") (pin "1") (pinfunction "1_1") (pintype "passive"))
    )
    (net (code "144") (name "Net-(R33-Pad1)") (class "Default")
      (node (ref "R33") (pin "1") (pinfunction "1_1") (pintype "passive"))
      (node (ref "XP27") (pin "1") (pinfunction "1_1") (pintype "passive"))
    )
    (net (code "145") (name "Net-(R34-Pad1)") (class "Default")
      (node (ref "R34") (pin "1") (pinfunction "1_1") (pintype "passive"))
      (node (ref "XP28") (pin "1") (pinfunction "1_1") (pintype "passive"))
    )
    (net (code "146") (name "Net-(R35-Pad1)") (class "Default")
      (node (ref "R35") (pin "1") (pinfunction "1_1") (pintype "passive"))
      (node (ref "XP29") (pin "1") (pinfunction "1_1") (pintype "passive"))
    )
    (net (code "147") (name "Net-(R36-Pad1)") (class "Default")
      (node (ref "R36") (pin "1") (pinfunction "1_1") (pintype "passive"))
      (node (ref "XP30") (pin "1") (pinfunction "1_1") (pintype "passive"))
    )
    (net (code "148") (name "Net-(R37-Pad1)") (class "Default")
      (node (ref "R37") (pin "1") (pinfunction "1_1") (pintype "passive"))
      (node (ref "XP31") (pin "1") (pinfunction "1_1") (pintype "passive"))
    )
    (net (code "149") (name "Net-(R38-Pad1)") (class "Default")
      (node (ref "R38") (pin "1") (pinfunction "1_1") (pintype "passive"))
      (node (ref "XP32") (pin "1") (pinfunction "1_1") (pintype "passive"))
    )
    (net (code "150") (name "Net-(R39-Pad1)") (class "Default")
      (node (ref "R39") (pin "1") (pinfunction "1_1") (pintype "passive"))
      (node (ref "XP33") (pin "1") (pinfunction "1_1") (pintype "passive"))
    )
    (net (code "151") (name "Net-(R40-Pad1)") (class "Default")
      (node (ref "R40") (pin "1") (pinfunction "1_1") (pintype "passive"))
      (node (ref "XP34") (pin "1") (pinfunction "1_1") (pintype "passive"))
    )
    (net (code "152") (name "Net-(R41-Pad1)") (class "Default")
      (node (ref "R41") (pin "1") (pinfunction "1_1") (pintype "passive"))
      (node (ref "XP35") (pin "1") (pinfunction "1_1") (pintype "passive"))
    )
    (net (code "153") (name "Net-(R42-Pad1)") (class "Default")
      (node (ref "R42") (pin "1") (pinfunction "1_1") (pintype "passive"))
      (node (ref "XP36") (pin "1") (pinfunction "1_1") (pintype "passive"))
    )
    (net (code "154") (name "Net-(R43-Pad1)") (class "Default")
      (node (ref "R43") (pin "1") (pinfunction "1_1") (pintype "passive"))
      (node (ref "XP37") (pin "1") (pinfunction "1_1") (pintype "passive"))
    )
    (net (code "155") (name "Net-(R44-Pad1)") (class "Default")
      (node (ref "R44") (pin "1") (pinfunction "1_1") (pintype "passive"))
      (node (ref "XP38") (pin "1") (pinfunction "1_1") (pintype "passive"))
    )
    (net (code "156") (name "Net-(R45-Pad1)") (class "Default")
      (node (ref "R45") (pin "1") (pinfunction "1_1") (pintype "passive"))
      (node (ref "XP39") (pin "1") (pinfunction "1_1") (pintype "passive"))
    )
    (net (code "157") (name "Net-(R46-Pad1)") (class "Default")
      (node (ref "R46") (pin "1") (pinfunction "1_1") (pintype "passive"))
      (node (ref "XP40") (pin "1") (pinfunction "1_1") (pintype "passive"))
    )
    (net (code "158") (name "Net-(R47-Pad1)") (class "Default")
      (node (ref "R47") (pin "1") (pinfunction "1_1") (pintype "passive"))
      (node (ref "XP41") (pin "1") (pinfunction "1_1") (pintype "passive"))
    )
    (net (code "159") (name "Net-(R48-Pad1)") (class "Default")
      (node (ref "R48") (pin "1") (pinfunction "1_1") (pintype "passive"))
      (node (ref "XP42") (pin "1") (pinfunction "1_1") (pintype "passive"))
    )
    (net (code "160") (name "Net-(R49-Pad1)") (class "Default")
      (node (ref "R49") (pin "1") (pinfunction "1_1") (pintype "passive"))
      (node (ref "XP43") (pin "1") (pinfunction "1_1") (pintype "passive"))
    )
    (net (code "161") (name "Net-(R50-Pad1)") (class "Default")
      (node (ref "R50") (pin "1") (pinfunction "1_1") (pintype "passive"))
      (node (ref "XP44") (pin "1") (pinfunction "1_1") (pintype "passive"))
    )
    (net (code "162") (name "Net-(R51-Pad1)") (class "Default")
      (node (ref "R51") (pin "1") (pinfunction "1_1") (pintype "passive"))
      (node (ref "XP45") (pin "1") (pinfunction "1_1") (pintype "passive"))
    )
    (net (code "163") (name "Net-(R52-Pad1)") (class "Default")
      (node (ref "R52") (pin "1") (pinfunction "1_1") (pintype "passive"))
      (node (ref "XP46") (pin "1") (pinfunction "1_1") (pintype "passive"))
    )
    (net (code "164") (name "Net-(R55-Pad2)") (class "Default")
      (node (ref "R55") (pin "2") (pinfunction "2_2") (pintype "passive"))
      (node (ref "XP92") (pin "1") (pinfunction "1_1") (pintype "passive"))
    )
    (net (code "165") (name "Net-(R56-Pad2)") (class "Default")
      (node (ref "R56") (pin "2") (pinfunction "2_2") (pintype "passive"))
      (node (ref "XP93") (pin "1") (pinfunction "1_1") (pintype "passive"))
    )
    (net (code "166") (name "Net-(R57-Pad2)") (class "Default")
      (node (ref "R57") (pin "2") (pinfunction "2_2") (pintype "passive"))
      (node (ref "XP47") (pin "1") (pinfunction "1_1") (pintype "passive"))
    )
    (net (code "167") (name "Net-(R58-Pad2)") (class "Default")
      (node (ref "R58") (pin "2") (pinfunction "2_2") (pintype "passive"))
      (node (ref "XP48") (pin "1") (pinfunction "1_1") (pintype "passive"))
    )
    (net (code "168") (name "Net-(R59-Pad2)") (class "Default")
      (node (ref "R59") (pin "2") (pinfunction "2_2") (pintype "passive"))
      (node (ref "XP49") (pin "1") (pinfunction "1_1") (pintype "passive"))
    )
    (net (code "169") (name "Net-(R60-Pad2)") (class "Default")
      (node (ref "R60") (pin "2") (pinfunction "2_2") (pintype "passive"))
      (node (ref "XP50") (pin "1") (pinfunction "1_1") (pintype "passive"))
    )
    (net (code "170") (name "Net-(R61-Pad2)") (class "Default")
      (node (ref "R61") (pin "2") (pinfunction "2_2") (pintype "passive"))
      (node (ref "XP51") (pin "1") (pinfunction "1_1") (pintype "passive"))
    )
    (net (code "171") (name "Net-(R62-Pad2)") (class "Default")
      (node (ref "R62") (pin "2") (pinfunction "2_2") (pintype "passive"))
      (node (ref "XP52") (pin "1") (pinfunction "1_1") (pintype "passive"))
    )
    (net (code "172") (name "Net-(R63-Pad2)") (class "Default")
      (node (ref "R63") (pin "2") (pinfunction "2_2") (pintype "passive"))
      (node (ref "XP53") (pin "1") (pinfunction "1_1") (pintype "passive"))
    )
    (net (code "173") (name "Net-(R64-Pad2)") (class "Default")
      (node (ref "R64") (pin "2") (pinfunction "2_2") (pintype "passive"))
      (node (ref "XP54") (pin "1") (pinfunction "1_1") (pintype "passive"))
    )
    (net (code "174") (name "Net-(R65-Pad2)") (class "Default")
      (node (ref "R65") (pin "2") (pinfunction "2_2") (pintype "passive"))
      (node (ref "XP55") (pin "1") (pinfunction "1_1") (pintype "passive"))
    )
    (net (code "175") (name "Net-(R66-Pad2)") (class "Default")
      (node (ref "R66") (pin "2") (pinfunction "2_2") (pintype "passive"))
      (node (ref "XP56") (pin "1") (pinfunction "1_1") (pintype "passive"))
    )
    (net (code "176") (name "Net-(R67-Pad2)") (class "Default")
      (node (ref "R67") (pin "2") (pinfunction "2_2") (pintype "passive"))
      (node (ref "XP57") (pin "1") (pinfunction "1_1") (pintype "passive"))
    )
    (net (code "177") (name "Net-(R68-Pad2)") (class "Default")
      (node (ref "R68") (pin "2") (pinfunction "2_2") (pintype "passive"))
      (node (ref "XP58") (pin "1") (pinfunction "1_1") (pintype "passive"))
    )
    (net (code "178") (name "Net-(R70-Pad2)") (class "Default")
      (node (ref "R70") (pin "2") (pinfunction "2_2") (pintype "passive"))
      (node (ref "XP59") (pin "1") (pinfunction "1_1") (pintype "passive"))
    )
    (net (code "179") (name "Net-(R71-Pad2)") (class "Default")
      (node (ref "R71") (pin "2") (pinfunction "2_2") (pintype "passive"))
      (node (ref "XP60") (pin "1") (pinfunction "1_1") (pintype "passive"))
    )
    (net (code "180") (name "Net-(R72-Pad2)") (class "Default")
      (node (ref "R72") (pin "2") (pinfunction "2_2") (pintype "passive"))
      (node (ref "XP61") (pin "1") (pinfunction "1_1") (pintype "passive"))
    )
    (net (code "181") (name "Net-(R73-Pad2)") (class "Default")
      (node (ref "R73") (pin "2") (pinfunction "2_2") (pintype "passive"))
      (node (ref "XP62") (pin "1") (pinfunction "1_1") (pintype "passive"))
    )
    (net (code "182") (name "Net-(R74-Pad2)") (class "Default")
      (node (ref "R74") (pin "2") (pinfunction "2_2") (pintype "passive"))
      (node (ref "XP63") (pin "1") (pinfunction "1_1") (pintype "passive"))
    )
    (net (code "183") (name "Net-(R75-Pad2)") (class "Default")
      (node (ref "R75") (pin "2") (pinfunction "2_2") (pintype "passive"))
      (node (ref "XP64") (pin "1") (pinfunction "1_1") (pintype "passive"))
    )
    (net (code "184") (name "Net-(R78-Pad2)") (class "Default")
      (node (ref "R78") (pin "2") (pinfunction "2_2") (pintype "passive"))
      (node (ref "XP67") (pin "1") (pinfunction "1_1") (pintype "passive"))
    )
    (net (code "185") (name "Net-(R79-Pad2)") (class "Default")
      (node (ref "R79") (pin "2") (pinfunction "2_2") (pintype "passive"))
      (node (ref "XP68") (pin "1") (pinfunction "1_1") (pintype "passive"))
    )
    (net (code "186") (name "Net-(R80-Pad2)") (class "Default")
      (node (ref "R80") (pin "2") (pinfunction "2_2") (pintype "passive"))
      (node (ref "XP69") (pin "1") (pinfunction "1_1") (pintype "passive"))
    )
    (net (code "187") (name "Net-(R81-Pad2)") (class "Default")
      (node (ref "R81") (pin "2") (pinfunction "2_2") (pintype "passive"))
      (node (ref "XP70") (pin "1") (pinfunction "1_1") (pintype "passive"))
    )
    (net (code "188") (name "Net-(R82-Pad2)") (class "Default")
      (node (ref "R82") (pin "2") (pinfunction "2_2") (pintype "passive"))
      (node (ref "XP71") (pin "1") (pinfunction "1_1") (pintype "passive"))
    )
    (net (code "189") (name "Net-(R83-Pad2)") (class "Default")
      (node (ref "R83") (pin "2") (pinfunction "2_2") (pintype "passive"))
      (node (ref "XP72") (pin "1") (pinfunction "1_1") (pintype "passive"))
    )
    (net (code "190") (name "Net-(R84-Pad2)") (class "Default")
      (node (ref "R84") (pin "2") (pinfunction "2_2") (pintype "passive"))
      (node (ref "XP73") (pin "1") (pinfunction "1_1") (pintype "passive"))
    )
    (net (code "191") (name "Net-(R85-Pad2)") (class "Default")
      (node (ref "R85") (pin "2") (pinfunction "2_2") (pintype "passive"))
      (node (ref "XP74") (pin "1") (pinfunction "1_1") (pintype "passive"))
    )
    (net (code "192") (name "Net-(R86-Pad2)") (class "Default")
      (node (ref "R86") (pin "2") (pinfunction "2_2") (pintype "passive"))
      (node (ref "XP75") (pin "1") (pinfunction "1_1") (pintype "passive"))
    )
    (net (code "193") (name "Net-(R87-Pad2)") (class "Default")
      (node (ref "R87") (pin "2") (pinfunction "2_2") (pintype "passive"))
      (node (ref "XP76") (pin "1") (pinfunction "1_1") (pintype "passive"))
    )
    (net (code "194") (name "Net-(R88-Pad2)") (class "Default")
      (node (ref "R88") (pin "2") (pinfunction "2_2") (pintype "passive"))
      (node (ref "XP77") (pin "1") (pinfunction "1_1") (pintype "passive"))
    )
    (net (code "195") (name "Net-(R89-Pad2)") (class "Default")
      (node (ref "R89") (pin "2") (pinfunction "2_2") (pintype "passive"))
      (node (ref "XP78") (pin "1") (pinfunction "1_1") (pintype "passive"))
    )
    (net (code "196") (name "Net-(R90-Pad2)") (class "Default")
      (node (ref "R90") (pin "2") (pinfunction "2_2") (pintype "passive"))
      (node (ref "XP79") (pin "1") (pinfunction "1_1") (pintype "passive"))
    )
    (net (code "197") (name "Net-(R91-Pad2)") (class "Default")
      (node (ref "R91") (pin "2") (pinfunction "2_2") (pintype "passive"))
      (node (ref "XP80") (pin "1") (pinfunction "1_1") (pintype "passive"))
    )
    (net (code "198") (name "Net-(R92-Pad2)") (class "Default")
      (node (ref "R92") (pin "2") (pinfunction "2_2") (pintype "passive"))
      (node (ref "XP81") (pin "1") (pinfunction "1_1") (pintype "passive"))
    )
    (net (code "199") (name "Net-(R93-Pad2)") (class "Default")
      (node (ref "R93") (pin "2") (pinfunction "2_2") (pintype "passive"))
      (node (ref "XP82") (pin "1") (pinfunction "1_1") (pintype "passive"))
    )
    (net (code "200") (name "Net-(R94-Pad2)") (class "Default")
      (node (ref "R94") (pin "2") (pinfunction "2_2") (pintype "passive"))
      (node (ref "XP83") (pin "1") (pinfunction "1_1") (pintype "passive"))
    )
    (net (code "201") (name "Net-(R95-Pad2)") (class "Default")
      (node (ref "R95") (pin "2") (pinfunction "2_2") (pintype "passive"))
      (node (ref "XP84") (pin "1") (pinfunction "1_1") (pintype "passive"))
    )
    (net (code "202") (name "Net-(R96-Pad2)") (class "Default")
      (node (ref "R96") (pin "2") (pinfunction "2_2") (pintype "passive"))
      (node (ref "XP85") (pin "1") (pinfunction "1_1") (pintype "passive"))
    )
    (net (code "203") (name "Net-(R97-Pad2)") (class "Default")
      (node (ref "R97") (pin "2") (pinfunction "2_2") (pintype "passive"))
      (node (ref "XP86") (pin "1") (pinfunction "1_1") (pintype "passive"))
    )
    (net (code "204") (name "Net-(R98-Pad2)") (class "Default")
      (node (ref "R98") (pin "2") (pinfunction "2_2") (pintype "passive"))
      (node (ref "XP87") (pin "1") (pinfunction "1_1") (pintype "passive"))
    )
    (net (code "205") (name "Net-(R99-Pad2)") (class "Default")
      (node (ref "R99") (pin "2") (pinfunction "2_2") (pintype "passive"))
      (node (ref "XP88") (pin "1") (pinfunction "1_1") (pintype "passive"))
    )
    (net (code "206") (name "Net-(R100-Pad2)") (class "Default")
      (node (ref "R100") (pin "2") (pinfunction "2_2") (pintype "passive"))
      (node (ref "XP89") (pin "1") (pinfunction "1_1") (pintype "passive"))
    )
    (net (code "207") (name "Net-(R101-Pad2)") (class "Default")
      (node (ref "R101") (pin "2") (pinfunction "2_2") (pintype "passive"))
      (node (ref "XP90") (pin "1") (pinfunction "1_1") (pintype "passive"))
    )
    (net (code "208") (name "Net-(R102-Pad2)") (class "Default")
      (node (ref "R102") (pin "2") (pinfunction "2_2") (pintype "passive"))
      (node (ref "XP91") (pin "1") (pinfunction "1_1") (pintype "passive"))
    )
    (net (code "209") (name "Net-(VD1-A)") (class "Default")
      (node (ref "C31") (pin "1") (pinfunction "1_1") (pintype "passive"))
      (node (ref "R107") (pin "2") (pinfunction "2_2") (pintype "passive"))
      (node (ref "VD1") (pin "1") (pinfunction "A_1") (pintype "passive"))
    )
    (net (code "210") (name "Net-(XS1-Pad1)") (class "Default")
      (node (ref "XS1") (pin "1") (pinfunction "1_1") (pintype "passive"))
      (node (ref "ZL3") (pin "1") (pinfunction "1_1") (pintype "passive"))
    )
    (net (code "211") (name "nReset") (class "Default")
      (node (ref "DD1") (pin "86") (pinfunction "CONF_DONE_86") (pintype "bidirectional"))
      (node (ref "R107") (pin "1") (pinfunction "1_1") (pintype "passive"))
      (node (ref "R2") (pin "1") (pinfunction "1_1") (pintype "passive"))
      (node (ref "R69") (pin "2") (pinfunction "2_2") (pintype "passive"))
      (node (ref "VD1") (pin "2") (pinfunction "K_2") (pintype "passive"))
      (node (ref "XP1") (pin "3") (pinfunction "3_3") (pintype "passive"))
    )
    (net (code "212") (name "unconnected-(DD1-nCEO-Pad20)") (class "Default")
      (node (ref "DD1") (pin "20") (pinfunction "nCEO_20") (pintype "output+no_connect"))
    )
    (net (code "213") (name "unconnected-(XP2-Pad6)") (class "Default")
      (node (ref "XP2") (pin "6") (pinfunction "6_6") (pintype "passive"))
    )
    (net (code "214") (name "unconnected-(XP2-Pad7)") (class "Default")
      (node (ref "XP2") (pin "7") (pinfunction "7_7") (pintype "passive"))
    )
    (net (code "215") (name "unconnected-(XP2-Pad8)") (class "Default")
      (node (ref "XP2") (pin "8") (pinfunction "8_8") (pintype "passive"))
    )
    (net (code "216") (name "unconnected-(XS1-Pad2)") (class "Default")
      (node (ref "XS1") (pin "2") (pinfunction "2_2") (pintype "passive"))
    )
    (net (code "217") (name "unconnected-(XS1-Pad3)") (class "Default")
      (node (ref "XS1") (pin "3") (pinfunction "3_3") (pintype "passive"))
    )
    (net (code "218") (name "unconnected-(XS1-Pad4)") (class "Default")
      (node (ref "XS1") (pin "4") (pinfunction "4_4") (pintype "passive"))
    )
  )
)
